# haasoscope_pro_adc_board_-_no_blind.net
KiCad netlist of a schematic drawn in EAGLE
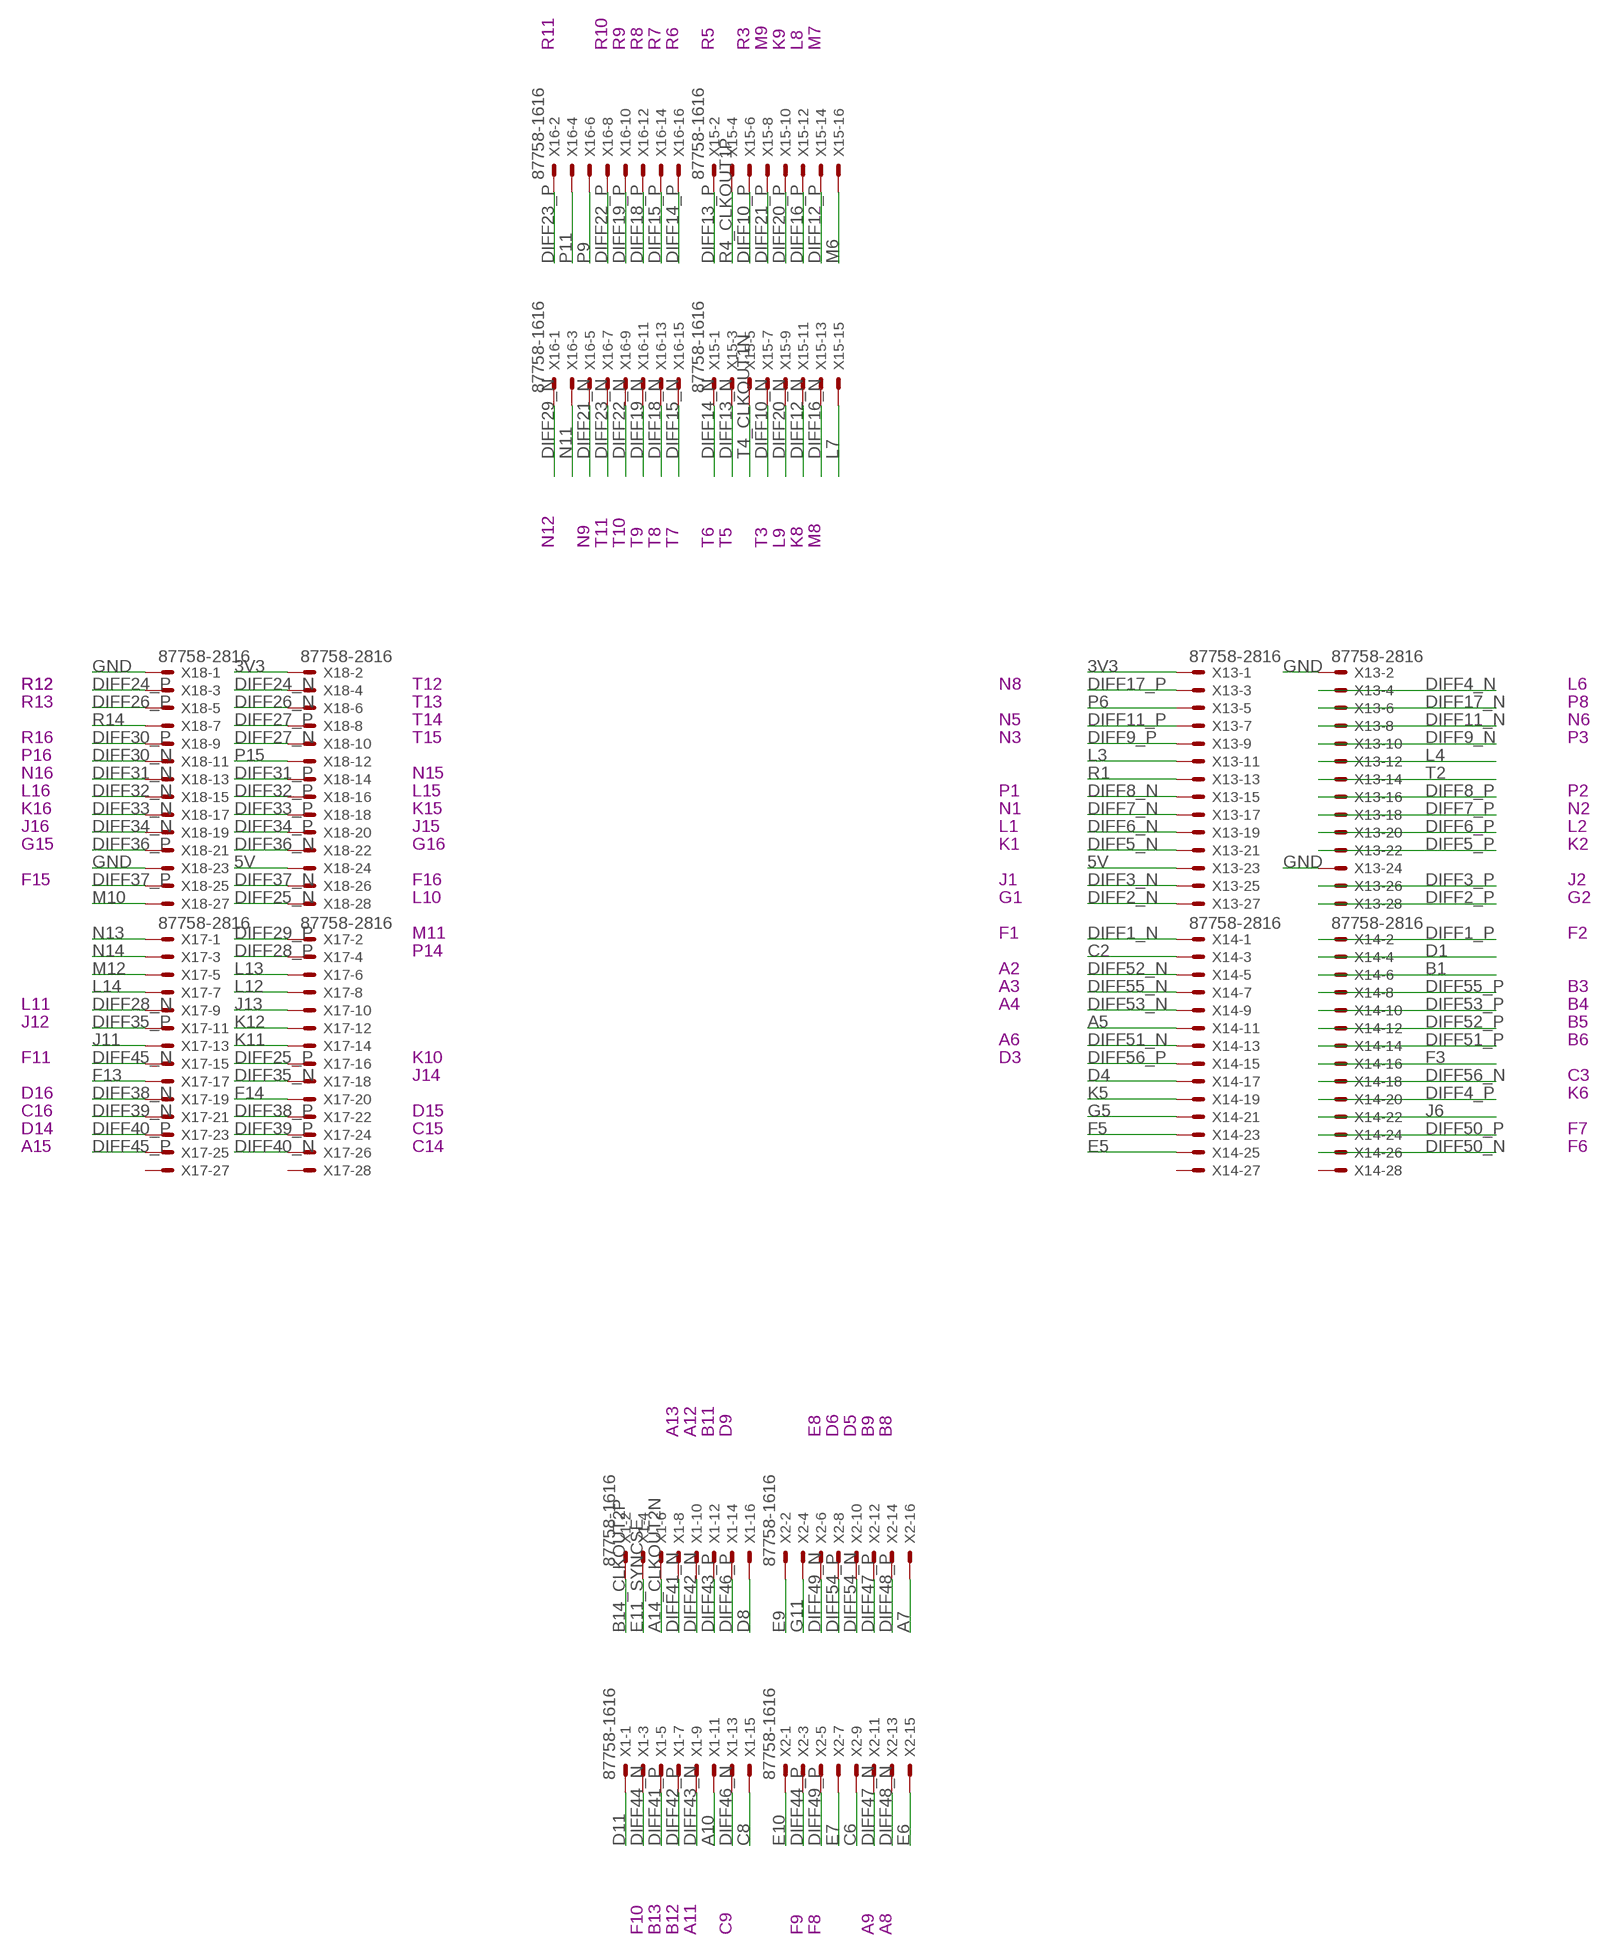
[diagram p0: schematic, sheet 1]
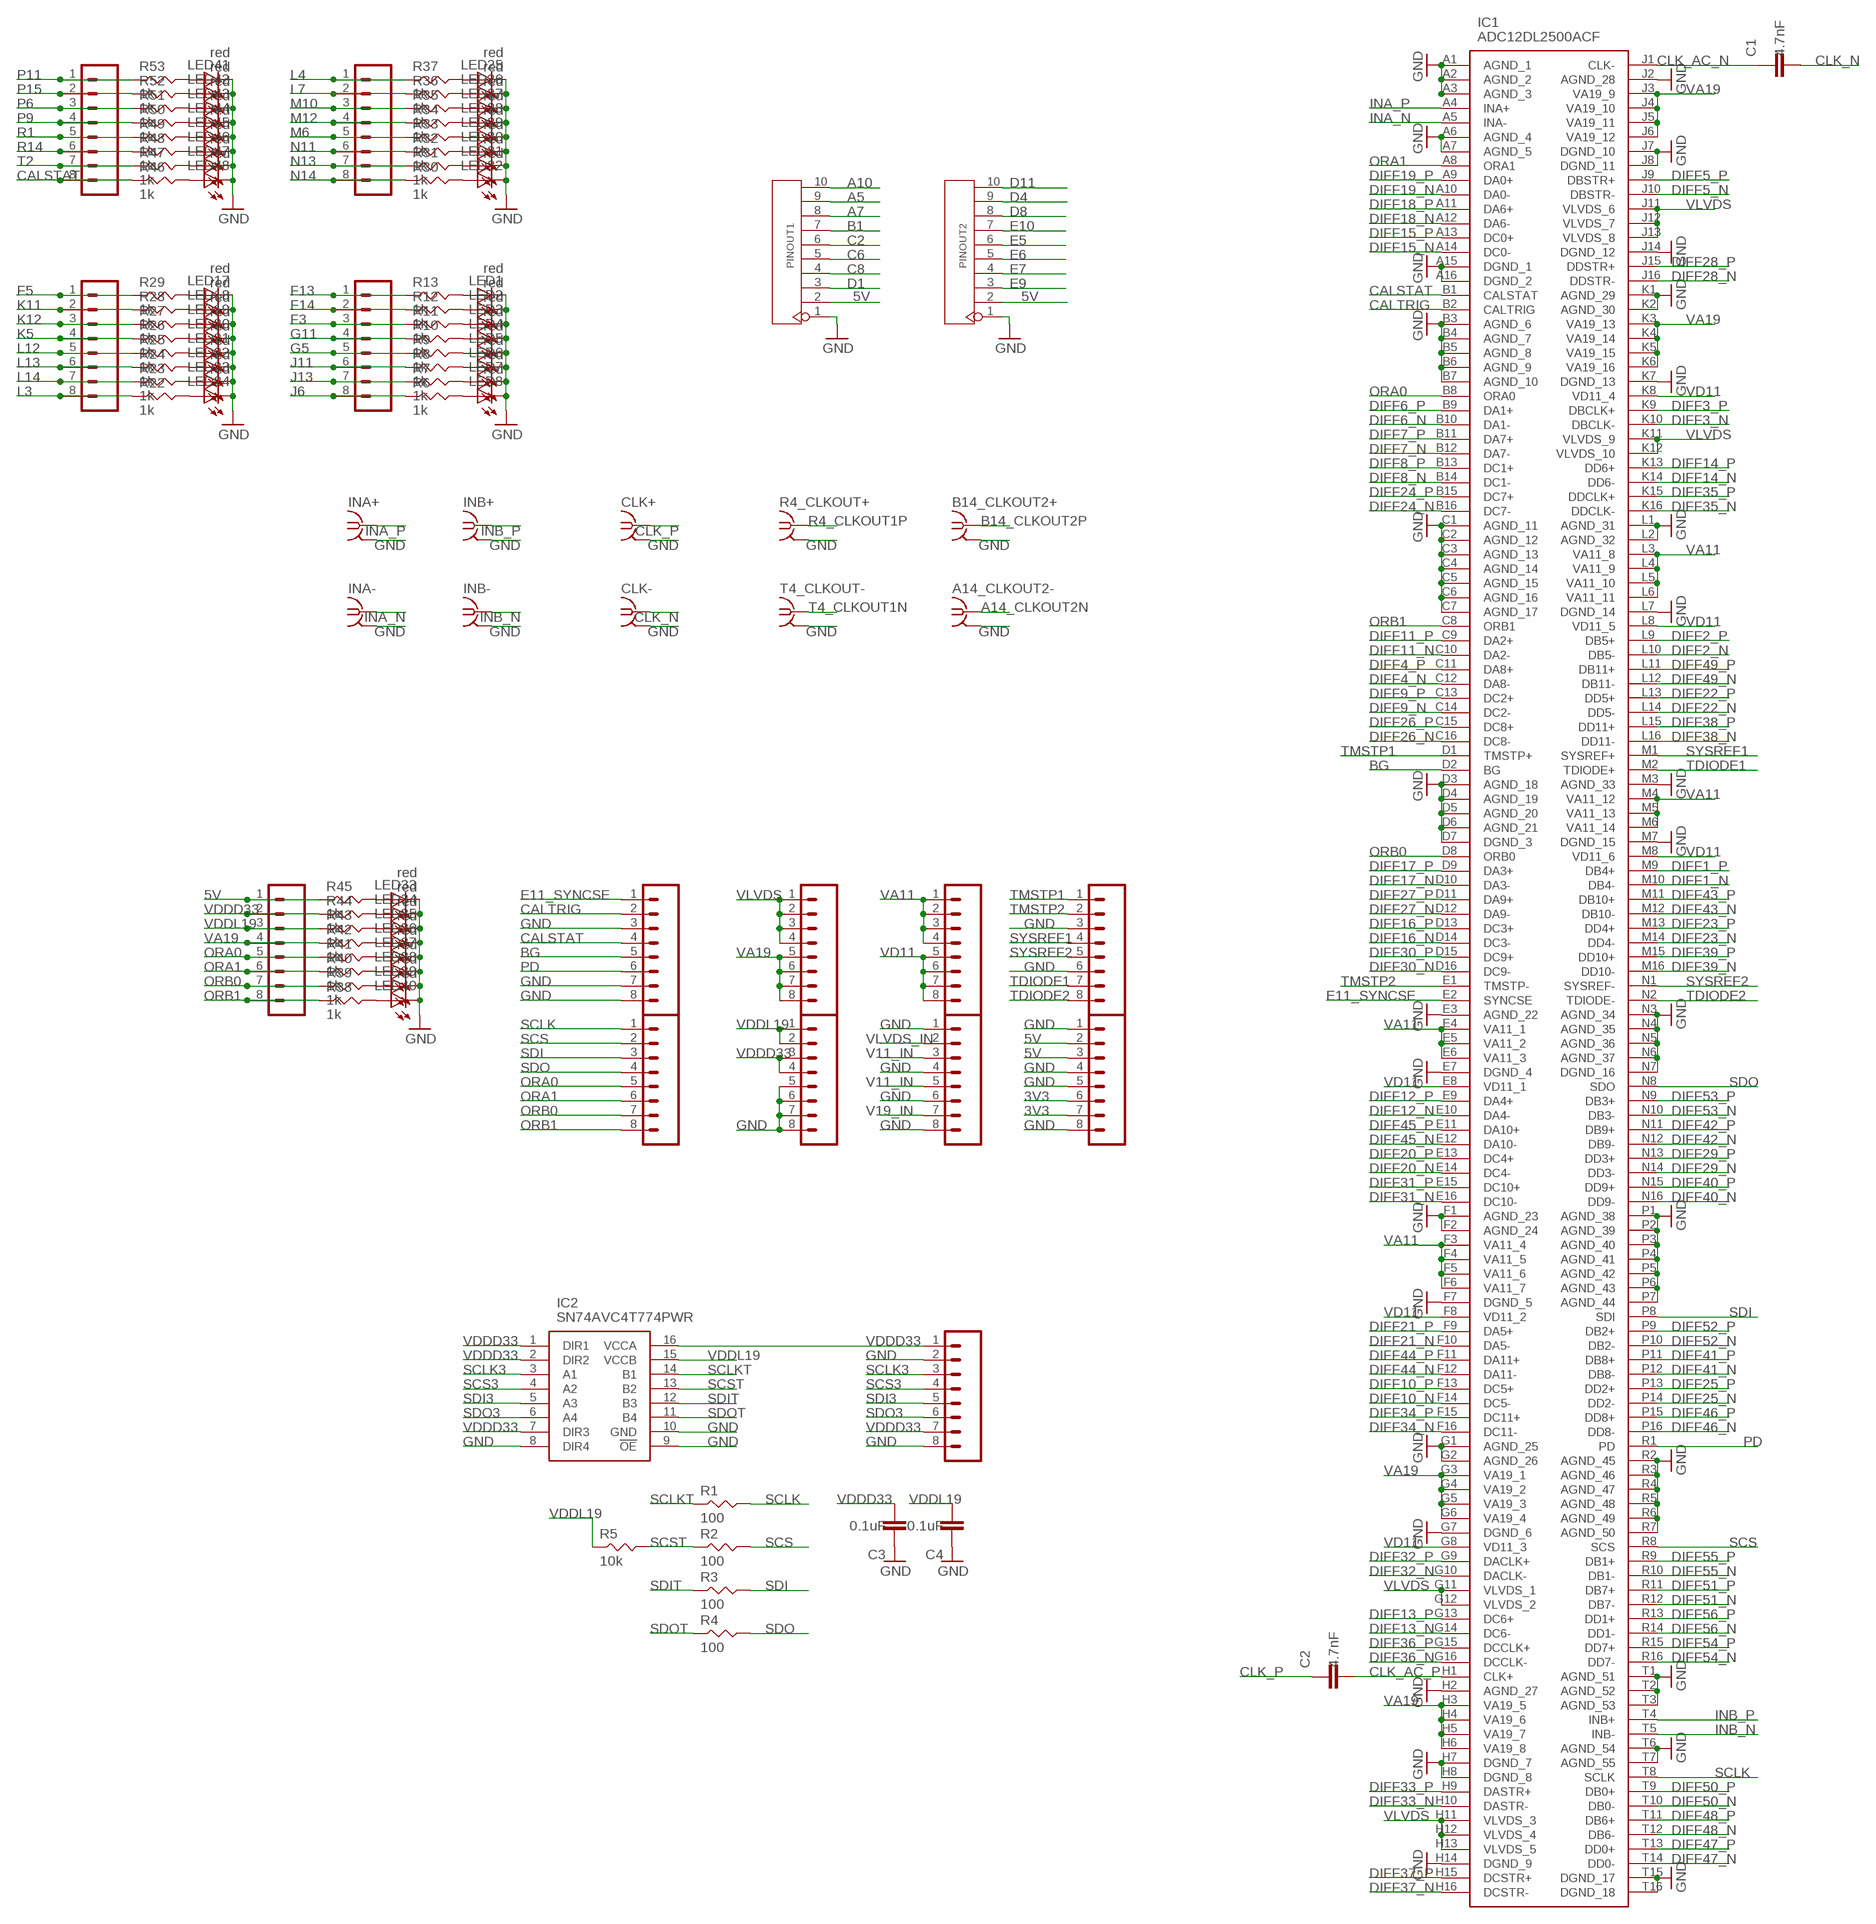
[diagram p1: schematic, sheet 2]
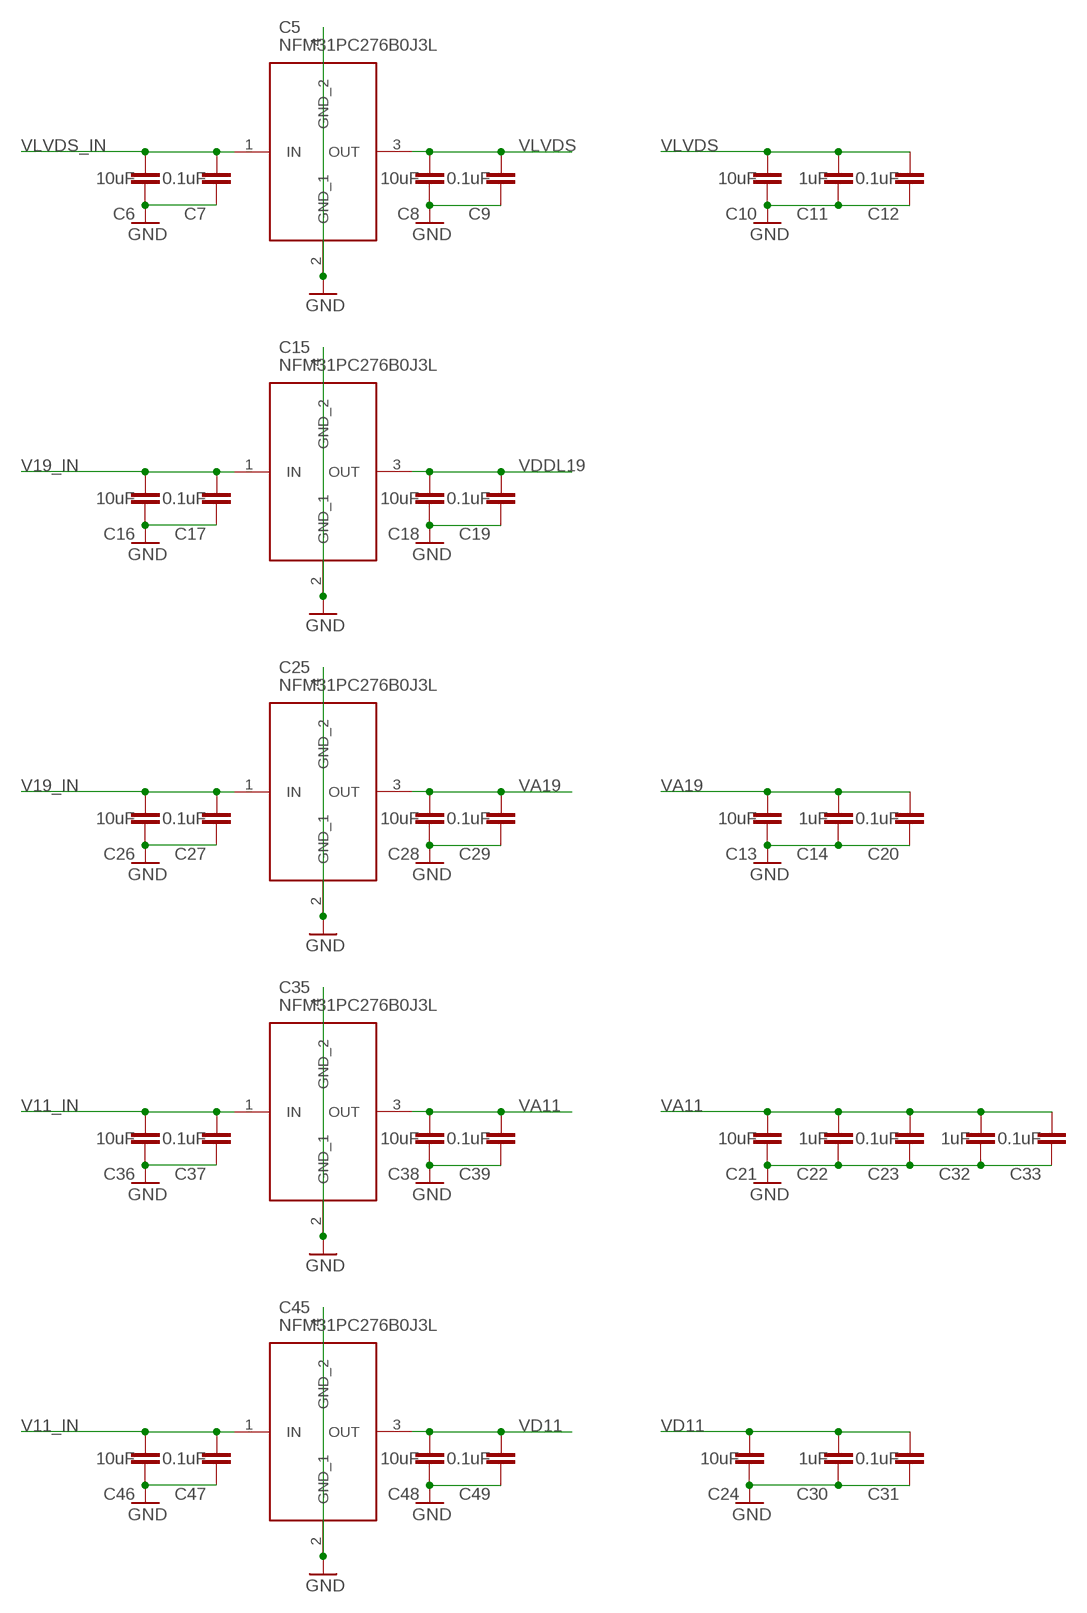
[diagram p2: schematic, sheet 3]

(export (version "E")
  (design (tool "Eeschema 10.0.6"))
  (components
    (comp (ref "C5")
      (value "NFM31PC276B0J3L")
      (footprint "eagle-import:NFM31HK103R1H3L")
      (fields (field (name "MOUSER_PART_NUMBER") "81-NFM31PC276B0J3L"))
      (libsource (lib "eagle-import") (part "NFM31PC276B0J3L"))
    )
    (comp (ref "C6")
      (value "10uF")
      (footprint "eagle-import:RESC0805_N")
      (libsource (lib "eagle-import") (part "CAPACITOR_0805_N"))
    )
    (comp (ref "C7")
      (value "0.1uF")
      (footprint "eagle-import:RESC0402_N")
      (libsource (lib "eagle-import") (part "CAPACITOR_0402_N"))
    )
    (comp (ref "C8")
      (value "10uF")
      (footprint "eagle-import:RESC0805_N")
      (libsource (lib "eagle-import") (part "CAPACITOR_0805_N"))
    )
    (comp (ref "C9")
      (value "0.1uF")
      (footprint "eagle-import:RESC0402_N")
      (libsource (lib "eagle-import") (part "CAPACITOR_0402_N"))
    )
    (comp (ref "C10")
      (value "10uF")
      (footprint "eagle-import:RESC0805_N")
      (libsource (lib "eagle-import") (part "CAPACITOR_0805_N"))
    )
    (comp (ref "C11")
      (value "1uF")
      (footprint "eagle-import:RESC0402_N")
      (libsource (lib "eagle-import") (part "CAPACITOR_0402_N"))
    )
    (comp (ref "C12")
      (value "0.1uF")
      (footprint "eagle-import:RESC0402_N")
      (libsource (lib "eagle-import") (part "CAPACITOR_0402_N"))
    )
    (comp (ref "C13")
      (value "10uF")
      (footprint "eagle-import:RESC0805_N")
      (libsource (lib "eagle-import") (part "CAPACITOR_0805_N"))
    )
    (comp (ref "C14")
      (value "1uF")
      (footprint "eagle-import:RESC0402_N")
      (libsource (lib "eagle-import") (part "CAPACITOR_0402_N"))
    )
    (comp (ref "C15")
      (value "NFM31PC276B0J3L")
      (footprint "eagle-import:NFM31HK103R1H3L")
      (fields (field (name "MOUSER_PART_NUMBER") "81-NFM31PC276B0J3L"))
      (libsource (lib "eagle-import") (part "NFM31PC276B0J3L"))
    )
    (comp (ref "C16")
      (value "10uF")
      (footprint "eagle-import:RESC0805_N")
      (libsource (lib "eagle-import") (part "CAPACITOR_0805_N"))
    )
    (comp (ref "C17")
      (value "0.1uF")
      (footprint "eagle-import:RESC0402_N")
      (libsource (lib "eagle-import") (part "CAPACITOR_0402_N"))
    )
    (comp (ref "C18")
      (value "10uF")
      (footprint "eagle-import:RESC0805_N")
      (libsource (lib "eagle-import") (part "CAPACITOR_0805_N"))
    )
    (comp (ref "C19")
      (value "0.1uF")
      (footprint "eagle-import:RESC0402_N")
      (libsource (lib "eagle-import") (part "CAPACITOR_0402_N"))
    )
    (comp (ref "C20")
      (value "0.1uF")
      (footprint "eagle-import:RESC0402_N")
      (libsource (lib "eagle-import") (part "CAPACITOR_0402_N"))
    )
    (comp (ref "C21")
      (value "10uF")
      (footprint "eagle-import:RESC0805_N")
      (libsource (lib "eagle-import") (part "CAPACITOR_0805_N"))
    )
    (comp (ref "C22")
      (value "1uF")
      (footprint "eagle-import:RESC0402_N")
      (libsource (lib "eagle-import") (part "CAPACITOR_0402_N"))
    )
    (comp (ref "C23")
      (value "0.1uF")
      (footprint "eagle-import:RESC0402_N")
      (libsource (lib "eagle-import") (part "CAPACITOR_0402_N"))
    )
    (comp (ref "C24")
      (value "10uF")
      (footprint "eagle-import:RESC0805_N")
      (libsource (lib "eagle-import") (part "CAPACITOR_0805_N"))
    )
    (comp (ref "C25")
      (value "NFM31PC276B0J3L")
      (footprint "eagle-import:NFM31HK103R1H3L")
      (fields (field (name "MOUSER_PART_NUMBER") "81-NFM31PC276B0J3L"))
      (libsource (lib "eagle-import") (part "NFM31PC276B0J3L"))
    )
    (comp (ref "C26")
      (value "10uF")
      (footprint "eagle-import:RESC0805_N")
      (libsource (lib "eagle-import") (part "CAPACITOR_0805_N"))
    )
    (comp (ref "C27")
      (value "0.1uF")
      (footprint "eagle-import:RESC0402_N")
      (libsource (lib "eagle-import") (part "CAPACITOR_0402_N"))
    )
    (comp (ref "C28")
      (value "10uF")
      (footprint "eagle-import:RESC0805_N")
      (libsource (lib "eagle-import") (part "CAPACITOR_0805_N"))
    )
    (comp (ref "C29")
      (value "0.1uF")
      (footprint "eagle-import:RESC0402_N")
      (libsource (lib "eagle-import") (part "CAPACITOR_0402_N"))
    )
    (comp (ref "C30")
      (value "1uF")
      (footprint "eagle-import:RESC0402_N")
      (libsource (lib "eagle-import") (part "CAPACITOR_0402_N"))
    )
    (comp (ref "C31")
      (value "0.1uF")
      (footprint "eagle-import:RESC0402_N")
      (libsource (lib "eagle-import") (part "CAPACITOR_0402_N"))
    )
    (comp (ref "C32")
      (value "1uF")
      (footprint "eagle-import:RESC0402_N")
      (libsource (lib "eagle-import") (part "CAPACITOR_0402_N"))
    )
    (comp (ref "C33")
      (value "0.1uF")
      (footprint "eagle-import:RESC0402_N")
      (libsource (lib "eagle-import") (part "CAPACITOR_0402_N"))
    )
    (comp (ref "C35")
      (value "NFM31PC276B0J3L")
      (footprint "eagle-import:NFM31HK103R1H3L")
      (fields (field (name "MOUSER_PART_NUMBER") "81-NFM31PC276B0J3L"))
      (libsource (lib "eagle-import") (part "NFM31PC276B0J3L"))
    )
    (comp (ref "C36")
      (value "10uF")
      (footprint "eagle-import:RESC0805_N")
      (libsource (lib "eagle-import") (part "CAPACITOR_0805_N"))
    )
    (comp (ref "C37")
      (value "0.1uF")
      (footprint "eagle-import:RESC0402_N")
      (libsource (lib "eagle-import") (part "CAPACITOR_0402_N"))
    )
    (comp (ref "C38")
      (value "10uF")
      (footprint "eagle-import:RESC0805_N")
      (libsource (lib "eagle-import") (part "CAPACITOR_0805_N"))
    )
    (comp (ref "C39")
      (value "0.1uF")
      (footprint "eagle-import:RESC0402_N")
      (libsource (lib "eagle-import") (part "CAPACITOR_0402_N"))
    )
    (comp (ref "C45")
      (value "NFM31PC276B0J3L")
      (footprint "eagle-import:NFM31HK103R1H3L")
      (fields (field (name "MOUSER_PART_NUMBER") "81-NFM31PC276B0J3L"))
      (libsource (lib "eagle-import") (part "NFM31PC276B0J3L"))
    )
    (comp (ref "C46")
      (value "10uF")
      (footprint "eagle-import:RESC0805_N")
      (libsource (lib "eagle-import") (part "CAPACITOR_0805_N"))
    )
    (comp (ref "C47")
      (value "0.1uF")
      (footprint "eagle-import:RESC0402_N")
      (libsource (lib "eagle-import") (part "CAPACITOR_0402_N"))
    )
    (comp (ref "C48")
      (value "10uF")
      (footprint "eagle-import:RESC0805_N")
      (libsource (lib "eagle-import") (part "CAPACITOR_0805_N"))
    )
    (comp (ref "C49")
      (value "0.1uF")
      (footprint "eagle-import:RESC0402_N")
      (libsource (lib "eagle-import") (part "CAPACITOR_0402_N"))
    )
    (comp (ref "X1")
      (value "87758-1616")
      (footprint "eagle-import:87758-1616")
      (fields (field (name "MF") "MOLEX"))
      (libsource (lib "eagle-import") (part "87758-1616"))
    )
    (comp (ref "X2")
      (value "87758-1616")
      (footprint "eagle-import:87758-1616")
      (fields (field (name "MF") "MOLEX"))
      (libsource (lib "eagle-import") (part "87758-1616"))
    )
    (comp (ref "X13")
      (value "87758-2816")
      (footprint "eagle-import:87758-2816")
      (fields (field (name "MF") "MOLEX"))
      (libsource (lib "eagle-import") (part "87758-2816"))
    )
    (comp (ref "X14")
      (value "87758-2816")
      (footprint "eagle-import:87758-2816")
      (fields (field (name "MF") "MOLEX"))
      (libsource (lib "eagle-import") (part "87758-2816"))
    )
    (comp (ref "X15")
      (value "87758-1616")
      (footprint "eagle-import:87758-1616")
      (fields (field (name "MF") "MOLEX"))
      (libsource (lib "eagle-import") (part "87758-1616"))
    )
    (comp (ref "X16")
      (value "87758-1616")
      (footprint "eagle-import:87758-1616")
      (fields (field (name "MF") "MOLEX"))
      (libsource (lib "eagle-import") (part "87758-1616"))
    )
    (comp (ref "X17")
      (value "87758-2816")
      (footprint "eagle-import:87758-2816")
      (fields (field (name "MF") "MOLEX"))
      (libsource (lib "eagle-import") (part "87758-2816"))
    )
    (comp (ref "X18")
      (value "87758-2816")
      (footprint "eagle-import:87758-2816")
      (fields (field (name "MF") "MOLEX"))
      (libsource (lib "eagle-import") (part "87758-2816"))
    )
    (comp (ref "A14_CLKOUT2-")
      (value "BU-SMB-V")
      (footprint "eagle-import:BU-SMB-V")
      (libsource (lib "eagle-import") (part "BU-SMB-V"))
    )
    (comp (ref "B14_CLKOUT2+")
      (value "BU-SMB-V")
      (footprint "eagle-import:BU-SMB-V")
      (libsource (lib "eagle-import") (part "BU-SMB-V"))
    )
    (comp (ref "C1")
      (value "4.7nF")
      (footprint "eagle-import:RESC0402_N")
      (libsource (lib "eagle-import") (part "CAPACITOR_0402_N"))
    )
    (comp (ref "C2")
      (value "4.7nF")
      (footprint "eagle-import:RESC0402_N")
      (libsource (lib "eagle-import") (part "CAPACITOR_0402_N"))
    )
    (comp (ref "C3")
      (value "0.1uF")
      (footprint "eagle-import:RESC0402_N")
      (libsource (lib "eagle-import") (part "CAPACITOR_0402_N"))
    )
    (comp (ref "C4")
      (value "0.1uF")
      (footprint "eagle-import:RESC0402_N")
      (libsource (lib "eagle-import") (part "CAPACITOR_0402_N"))
    )
    (comp (ref "CLK+")
      (value "BU-SMB-V")
      (footprint "eagle-import:BU-SMB-V")
      (libsource (lib "eagle-import") (part "BU-SMB-V"))
    )
    (comp (ref "CLK-")
      (value "BU-SMB-V")
      (footprint "eagle-import:BU-SMB-V")
      (libsource (lib "eagle-import") (part "BU-SMB-V"))
    )
    (comp (ref "IC1")
      (value "ADC12DL2500ACF")
      (footprint "eagle-import:BGA256C100P16X16_1700X1700X331")
      (fields (field (name "MANUFACTURER_PART_NUMBER") "ADC12DL500ACF"))
      (libsource (lib "eagle-import") (part "ADC12DL2500ACF"))
    )
    (comp (ref "IC2")
      (value "SN74AVC4T774PWR")
      (footprint "eagle-import:SOP65P640X120-16N")
      (fields (field (name "MOUSER_PART_NUMBER") "595-SN74AVC4T774PWR"))
      (libsource (lib "eagle-import") (part "SN74AVC4T774PWR"))
    )
    (comp (ref "INA+")
      (value "BU-SMB-V")
      (footprint "eagle-import:BU-SMB-V")
      (libsource (lib "eagle-import") (part "BU-SMB-V"))
    )
    (comp (ref "INA-")
      (value "BU-SMB-V")
      (footprint "eagle-import:BU-SMB-V")
      (libsource (lib "eagle-import") (part "BU-SMB-V"))
    )
    (comp (ref "INB+")
      (value "BU-SMB-V")
      (footprint "eagle-import:BU-SMB-V")
      (libsource (lib "eagle-import") (part "BU-SMB-V"))
    )
    (comp (ref "INB-")
      (value "BU-SMB-V")
      (footprint "eagle-import:BU-SMB-V")
      (libsource (lib "eagle-import") (part "BU-SMB-V"))
    )
    (comp (ref "J1")
      (value "8pin")
      (footprint "eagle-import:1X08")
      (libsource (lib "eagle-import") (part "CONN_08{dblquote}"))
    )
    (comp (ref "J2")
      (value "8pin")
      (footprint "eagle-import:1X08")
      (libsource (lib "eagle-import") (part "CONN_08{dblquote}"))
    )
    (comp (ref "J3")
      (value "8pin")
      (footprint "eagle-import:1X08")
      (libsource (lib "eagle-import") (part "CONN_08{dblquote}"))
    )
    (comp (ref "J4")
      (value "8pin")
      (footprint "eagle-import:1X08")
      (libsource (lib "eagle-import") (part "CONN_08{dblquote}"))
    )
    (comp (ref "J5")
      (value "8pin")
      (footprint "eagle-import:1X08")
      (libsource (lib "eagle-import") (part "CONN_08{dblquote}"))
    )
    (comp (ref "J6")
      (value "8pin")
      (footprint "eagle-import:1X08")
      (libsource (lib "eagle-import") (part "CONN_08{dblquote}"))
    )
    (comp (ref "J7")
      (value "8pin")
      (footprint "eagle-import:1X08")
      (libsource (lib "eagle-import") (part "CONN_08{dblquote}"))
    )
    (comp (ref "J8")
      (value "8pin")
      (footprint "eagle-import:1X08")
      (libsource (lib "eagle-import") (part "CONN_08{dblquote}"))
    )
    (comp (ref "J10")
      (value "8pin")
      (footprint "eagle-import:1X08")
      (libsource (lib "eagle-import") (part "CONN_08{dblquote}"))
    )
    (comp (ref "J11")
      (value "8pin")
      (footprint "eagle-import:1X08")
      (libsource (lib "eagle-import") (part "CONN_08{dblquote}"))
    )
    (comp (ref "J12")
      (value "8pin")
      (footprint "eagle-import:1X08")
      (libsource (lib "eagle-import") (part "CONN_08{dblquote}"))
    )
    (comp (ref "J13")
      (value "8pin")
      (footprint "eagle-import:1X08")
      (libsource (lib "eagle-import") (part "CONN_08{dblquote}"))
    )
    (comp (ref "J16")
      (value "8pin")
      (footprint "eagle-import:1X08")
      (libsource (lib "eagle-import") (part "CONN_08{dblquote}"))
    )
    (comp (ref "J17")
      (value "8pin")
      (footprint "eagle-import:1X08")
      (libsource (lib "eagle-import") (part "CONN_08{dblquote}"))
    )
    (comp (ref "LED1")
      (value "red")
      (footprint "eagle-import:CHIP-LED0603")
      (libsource (lib "eagle-import") (part "LEDCHIP-LED0603"))
    )
    (comp (ref "LED2")
      (value "red")
      (footprint "eagle-import:CHIP-LED0603")
      (libsource (lib "eagle-import") (part "LEDCHIP-LED0603"))
    )
    (comp (ref "LED3")
      (value "red")
      (footprint "eagle-import:CHIP-LED0603")
      (libsource (lib "eagle-import") (part "LEDCHIP-LED0603"))
    )
    (comp (ref "LED4")
      (value "red")
      (footprint "eagle-import:CHIP-LED0603")
      (libsource (lib "eagle-import") (part "LEDCHIP-LED0603"))
    )
    (comp (ref "LED5")
      (value "red")
      (footprint "eagle-import:CHIP-LED0603")
      (libsource (lib "eagle-import") (part "LEDCHIP-LED0603"))
    )
    (comp (ref "LED6")
      (value "red")
      (footprint "eagle-import:CHIP-LED0603")
      (libsource (lib "eagle-import") (part "LEDCHIP-LED0603"))
    )
    (comp (ref "LED7")
      (value "red")
      (footprint "eagle-import:CHIP-LED0603")
      (libsource (lib "eagle-import") (part "LEDCHIP-LED0603"))
    )
    (comp (ref "LED8")
      (value "red")
      (footprint "eagle-import:CHIP-LED0603")
      (libsource (lib "eagle-import") (part "LEDCHIP-LED0603"))
    )
    (comp (ref "LED17")
      (value "red")
      (footprint "eagle-import:CHIP-LED0603")
      (libsource (lib "eagle-import") (part "LEDCHIP-LED0603"))
    )
    (comp (ref "LED18")
      (value "red")
      (footprint "eagle-import:CHIP-LED0603")
      (libsource (lib "eagle-import") (part "LEDCHIP-LED0603"))
    )
    (comp (ref "LED19")
      (value "red")
      (footprint "eagle-import:CHIP-LED0603")
      (libsource (lib "eagle-import") (part "LEDCHIP-LED0603"))
    )
    (comp (ref "LED20")
      (value "red")
      (footprint "eagle-import:CHIP-LED0603")
      (libsource (lib "eagle-import") (part "LEDCHIP-LED0603"))
    )
    (comp (ref "LED21")
      (value "red")
      (footprint "eagle-import:CHIP-LED0603")
      (libsource (lib "eagle-import") (part "LEDCHIP-LED0603"))
    )
    (comp (ref "LED22")
      (value "red")
      (footprint "eagle-import:CHIP-LED0603")
      (libsource (lib "eagle-import") (part "LEDCHIP-LED0603"))
    )
    (comp (ref "LED23")
      (value "red")
      (footprint "eagle-import:CHIP-LED0603")
      (libsource (lib "eagle-import") (part "LEDCHIP-LED0603"))
    )
    (comp (ref "LED24")
      (value "red")
      (footprint "eagle-import:CHIP-LED0603")
      (libsource (lib "eagle-import") (part "LEDCHIP-LED0603"))
    )
    (comp (ref "LED25")
      (value "red")
      (footprint "eagle-import:CHIP-LED0603")
      (libsource (lib "eagle-import") (part "LEDCHIP-LED0603"))
    )
    (comp (ref "LED26")
      (value "red")
      (footprint "eagle-import:CHIP-LED0603")
      (libsource (lib "eagle-import") (part "LEDCHIP-LED0603"))
    )
    (comp (ref "LED27")
      (value "red")
      (footprint "eagle-import:CHIP-LED0603")
      (libsource (lib "eagle-import") (part "LEDCHIP-LED0603"))
    )
    (comp (ref "LED28")
      (value "red")
      (footprint "eagle-import:CHIP-LED0603")
      (libsource (lib "eagle-import") (part "LEDCHIP-LED0603"))
    )
    (comp (ref "LED29")
      (value "red")
      (footprint "eagle-import:CHIP-LED0603")
      (libsource (lib "eagle-import") (part "LEDCHIP-LED0603"))
    )
    (comp (ref "LED30")
      (value "red")
      (footprint "eagle-import:CHIP-LED0603")
      (libsource (lib "eagle-import") (part "LEDCHIP-LED0603"))
    )
    (comp (ref "LED31")
      (value "red")
      (footprint "eagle-import:CHIP-LED0603")
      (libsource (lib "eagle-import") (part "LEDCHIP-LED0603"))
    )
    (comp (ref "LED32")
      (value "red")
      (footprint "eagle-import:CHIP-LED0603")
      (libsource (lib "eagle-import") (part "LEDCHIP-LED0603"))
    )
    (comp (ref "LED33")
      (value "red")
      (footprint "eagle-import:CHIP-LED0603")
      (libsource (lib "eagle-import") (part "LEDCHIP-LED0603"))
    )
    (comp (ref "LED34")
      (value "red")
      (footprint "eagle-import:CHIP-LED0603")
      (libsource (lib "eagle-import") (part "LEDCHIP-LED0603"))
    )
    (comp (ref "LED35")
      (value "red")
      (footprint "eagle-import:CHIP-LED0603")
      (libsource (lib "eagle-import") (part "LEDCHIP-LED0603"))
    )
    (comp (ref "LED36")
      (value "red")
      (footprint "eagle-import:CHIP-LED0603")
      (libsource (lib "eagle-import") (part "LEDCHIP-LED0603"))
    )
    (comp (ref "LED37")
      (value "red")
      (footprint "eagle-import:CHIP-LED0603")
      (libsource (lib "eagle-import") (part "LEDCHIP-LED0603"))
    )
    (comp (ref "LED38")
      (value "red")
      (footprint "eagle-import:CHIP-LED0603")
      (libsource (lib "eagle-import") (part "LEDCHIP-LED0603"))
    )
    (comp (ref "LED39")
      (value "red")
      (footprint "eagle-import:CHIP-LED0603")
      (libsource (lib "eagle-import") (part "LEDCHIP-LED0603"))
    )
    (comp (ref "LED40")
      (value "red")
      (footprint "eagle-import:CHIP-LED0603")
      (libsource (lib "eagle-import") (part "LEDCHIP-LED0603"))
    )
    (comp (ref "LED41")
      (value "red")
      (footprint "eagle-import:CHIP-LED0603")
      (libsource (lib "eagle-import") (part "LEDCHIP-LED0603"))
    )
    (comp (ref "LED42")
      (value "red")
      (footprint "eagle-import:CHIP-LED0603")
      (libsource (lib "eagle-import") (part "LEDCHIP-LED0603"))
    )
    (comp (ref "LED43")
      (value "red")
      (footprint "eagle-import:CHIP-LED0603")
      (libsource (lib "eagle-import") (part "LEDCHIP-LED0603"))
    )
    (comp (ref "LED44")
      (value "red")
      (footprint "eagle-import:CHIP-LED0603")
      (libsource (lib "eagle-import") (part "LEDCHIP-LED0603"))
    )
    (comp (ref "LED45")
      (value "red")
      (footprint "eagle-import:CHIP-LED0603")
      (libsource (lib "eagle-import") (part "LEDCHIP-LED0603"))
    )
    (comp (ref "LED46")
      (value "red")
      (footprint "eagle-import:CHIP-LED0603")
      (libsource (lib "eagle-import") (part "LEDCHIP-LED0603"))
    )
    (comp (ref "LED47")
      (value "red")
      (footprint "eagle-import:CHIP-LED0603")
      (libsource (lib "eagle-import") (part "LEDCHIP-LED0603"))
    )
    (comp (ref "LED48")
      (value "red")
      (footprint "eagle-import:CHIP-LED0603")
      (libsource (lib "eagle-import") (part "LEDCHIP-LED0603"))
    )
    (comp (ref "PINOUT1")
      (value "YELLOW-10P-2.54")
      (footprint "eagle-import:H10-2.54")
      (fields (field (name "MPN") "F185-1110A1BSYC1"))
      (libsource (lib "eagle-import") (part "DIP-YELLOW-FEMALE-HEADER-VERT(10P-2.54)"))
    )
    (comp (ref "PINOUT2")
      (value "YELLOW-10P-2.54")
      (footprint "eagle-import:H10-2.54")
      (fields (field (name "MPN") "F185-1110A1BSYC1"))
      (libsource (lib "eagle-import") (part "DIP-YELLOW-FEMALE-HEADER-VERT(10P-2.54)"))
    )
    (comp (ref "R1")
      (value "100")
      (footprint "eagle-import:RES-0402")
      (libsource (lib "eagle-import") (part "RES-0402"))
    )
    (comp (ref "R2")
      (value "100")
      (footprint "eagle-import:RES-0402")
      (libsource (lib "eagle-import") (part "RES-0402"))
    )
    (comp (ref "R3")
      (value "100")
      (footprint "eagle-import:RES-0402")
      (libsource (lib "eagle-import") (part "RES-0402"))
    )
    (comp (ref "R4")
      (value "100")
      (footprint "eagle-import:RES-0402")
      (libsource (lib "eagle-import") (part "RES-0402"))
    )
    (comp (ref "R4_CLKOUT+")
      (value "BU-SMB-V")
      (footprint "eagle-import:BU-SMB-V")
      (libsource (lib "eagle-import") (part "BU-SMB-V"))
    )
    (comp (ref "R5")
      (value "10k")
      (footprint "eagle-import:RES-0402")
      (libsource (lib "eagle-import") (part "RES-0402"))
    )
    (comp (ref "R6")
      (value "1k")
      (footprint "eagle-import:RES-0402")
      (libsource (lib "eagle-import") (part "RES-0402"))
    )
    (comp (ref "R7")
      (value "1k")
      (footprint "eagle-import:RES-0402")
      (libsource (lib "eagle-import") (part "RES-0402"))
    )
    (comp (ref "R8")
      (value "1k")
      (footprint "eagle-import:RES-0402")
      (libsource (lib "eagle-import") (part "RES-0402"))
    )
    (comp (ref "R9")
      (value "1k")
      (footprint "eagle-import:RES-0402")
      (libsource (lib "eagle-import") (part "RES-0402"))
    )
    (comp (ref "R10")
      (value "1k")
      (footprint "eagle-import:RES-0402")
      (libsource (lib "eagle-import") (part "RES-0402"))
    )
    (comp (ref "R11")
      (value "1k")
      (footprint "eagle-import:RES-0402")
      (libsource (lib "eagle-import") (part "RES-0402"))
    )
    (comp (ref "R12")
      (value "1k")
      (footprint "eagle-import:RES-0402")
      (libsource (lib "eagle-import") (part "RES-0402"))
    )
    (comp (ref "R13")
      (value "1k")
      (footprint "eagle-import:RES-0402")
      (libsource (lib "eagle-import") (part "RES-0402"))
    )
    (comp (ref "R22")
      (value "1k")
      (footprint "eagle-import:RES-0402")
      (libsource (lib "eagle-import") (part "RES-0402"))
    )
    (comp (ref "R23")
      (value "1k")
      (footprint "eagle-import:RES-0402")
      (libsource (lib "eagle-import") (part "RES-0402"))
    )
    (comp (ref "R24")
      (value "1k")
      (footprint "eagle-import:RES-0402")
      (libsource (lib "eagle-import") (part "RES-0402"))
    )
    (comp (ref "R25")
      (value "1k")
      (footprint "eagle-import:RES-0402")
      (libsource (lib "eagle-import") (part "RES-0402"))
    )
    (comp (ref "R26")
      (value "1k")
      (footprint "eagle-import:RES-0402")
      (libsource (lib "eagle-import") (part "RES-0402"))
    )
    (comp (ref "R27")
      (value "1k")
      (footprint "eagle-import:RES-0402")
      (libsource (lib "eagle-import") (part "RES-0402"))
    )
    (comp (ref "R28")
      (value "1k")
      (footprint "eagle-import:RES-0402")
      (libsource (lib "eagle-import") (part "RES-0402"))
    )
    (comp (ref "R29")
      (value "1k")
      (footprint "eagle-import:RES-0402")
      (libsource (lib "eagle-import") (part "RES-0402"))
    )
    (comp (ref "R30")
      (value "1k")
      (footprint "eagle-import:RES-0402")
      (libsource (lib "eagle-import") (part "RES-0402"))
    )
    (comp (ref "R31")
      (value "1k")
      (footprint "eagle-import:RES-0402")
      (libsource (lib "eagle-import") (part "RES-0402"))
    )
    (comp (ref "R32")
      (value "1k")
      (footprint "eagle-import:RES-0402")
      (libsource (lib "eagle-import") (part "RES-0402"))
    )
    (comp (ref "R33")
      (value "1k")
      (footprint "eagle-import:RES-0402")
      (libsource (lib "eagle-import") (part "RES-0402"))
    )
    (comp (ref "R34")
      (value "1k")
      (footprint "eagle-import:RES-0402")
      (libsource (lib "eagle-import") (part "RES-0402"))
    )
    (comp (ref "R35")
      (value "1k")
      (footprint "eagle-import:RES-0402")
      (libsource (lib "eagle-import") (part "RES-0402"))
    )
    (comp (ref "R36")
      (value "1k")
      (footprint "eagle-import:RES-0402")
      (libsource (lib "eagle-import") (part "RES-0402"))
    )
    (comp (ref "R37")
      (value "1k")
      (footprint "eagle-import:RES-0402")
      (libsource (lib "eagle-import") (part "RES-0402"))
    )
    (comp (ref "R38")
      (value "1k")
      (footprint "eagle-import:RES-0402")
      (libsource (lib "eagle-import") (part "RES-0402"))
    )
    (comp (ref "R39")
      (value "1k")
      (footprint "eagle-import:RES-0402")
      (libsource (lib "eagle-import") (part "RES-0402"))
    )
    (comp (ref "R40")
      (value "1k")
      (footprint "eagle-import:RES-0402")
      (libsource (lib "eagle-import") (part "RES-0402"))
    )
    (comp (ref "R41")
      (value "1k")
      (footprint "eagle-import:RES-0402")
      (libsource (lib "eagle-import") (part "RES-0402"))
    )
    (comp (ref "R42")
      (value "1k")
      (footprint "eagle-import:RES-0402")
      (libsource (lib "eagle-import") (part "RES-0402"))
    )
    (comp (ref "R43")
      (value "1k")
      (footprint "eagle-import:RES-0402")
      (libsource (lib "eagle-import") (part "RES-0402"))
    )
    (comp (ref "R44")
      (value "1k")
      (footprint "eagle-import:RES-0402")
      (libsource (lib "eagle-import") (part "RES-0402"))
    )
    (comp (ref "R45")
      (value "1k")
      (footprint "eagle-import:RES-0402")
      (libsource (lib "eagle-import") (part "RES-0402"))
    )
    (comp (ref "R46")
      (value "1k")
      (footprint "eagle-import:RES-0402")
      (libsource (lib "eagle-import") (part "RES-0402"))
    )
    (comp (ref "R47")
      (value "1k")
      (footprint "eagle-import:RES-0402")
      (libsource (lib "eagle-import") (part "RES-0402"))
    )
    (comp (ref "R48")
      (value "1k")
      (footprint "eagle-import:RES-0402")
      (libsource (lib "eagle-import") (part "RES-0402"))
    )
    (comp (ref "R49")
      (value "1k")
      (footprint "eagle-import:RES-0402")
      (libsource (lib "eagle-import") (part "RES-0402"))
    )
    (comp (ref "R50")
      (value "1k")
      (footprint "eagle-import:RES-0402")
      (libsource (lib "eagle-import") (part "RES-0402"))
    )
    (comp (ref "R51")
      (value "1k")
      (footprint "eagle-import:RES-0402")
      (libsource (lib "eagle-import") (part "RES-0402"))
    )
    (comp (ref "R52")
      (value "1k")
      (footprint "eagle-import:RES-0402")
      (libsource (lib "eagle-import") (part "RES-0402"))
    )
    (comp (ref "R53")
      (value "1k")
      (footprint "eagle-import:RES-0402")
      (libsource (lib "eagle-import") (part "RES-0402"))
    )
    (comp (ref "T4_CLKOUT-")
      (value "BU-SMB-V")
      (footprint "eagle-import:BU-SMB-V")
      (libsource (lib "eagle-import") (part "BU-SMB-V"))
    )
  )
  (nets
    (net (code "1") (name "3V3") (class "Default")
      (node (ref "J6") (pin "6") (pinfunction "6_6") (pintype "passive"))
      (node (ref "J6") (pin "7") (pinfunction "7_7") (pintype "passive"))
      (node (ref "X13") (pin "1") (pinfunction "S_1") (pintype "passive"))
      (node (ref "X18") (pin "2") (pinfunction "S_2") (pintype "passive"))
    )
    (net (code "2") (name "5V") (class "Default")
      (node (ref "J12") (pin "1") (pinfunction "1_1") (pintype "passive"))
      (node (ref "J6") (pin "2") (pinfunction "2_2") (pintype "passive"))
      (node (ref "J6") (pin "3") (pinfunction "3_3") (pintype "passive"))
      (node (ref "PINOUT1") (pin "2") (pinfunction "2_2") (pintype "bidirectional"))
      (node (ref "PINOUT2") (pin "2") (pinfunction "2_2") (pintype "bidirectional"))
      (node (ref "R45") (pin "P$1") (pinfunction "P$1_P$1") (pintype "bidirectional"))
      (node (ref "X13") (pin "23") (pinfunction "S_23") (pintype "passive"))
      (node (ref "X18") (pin "24") (pinfunction "S_24") (pintype "passive"))
    )
    (net (code "3") (name "A5") (class "Default")
      (node (ref "PINOUT1") (pin "9") (pinfunction "9_9") (pintype "bidirectional"))
      (node (ref "X14") (pin "11") (pinfunction "S_11") (pintype "passive"))
    )
    (net (code "4") (name "A7") (class "Default")
      (node (ref "PINOUT1") (pin "8") (pinfunction "8_8") (pintype "bidirectional"))
      (node (ref "X2") (pin "16") (pinfunction "S_16") (pintype "passive"))
    )
    (net (code "5") (name "A10") (class "Default")
      (node (ref "PINOUT1") (pin "10") (pinfunction "10_10") (pintype "bidirectional"))
      (node (ref "X1") (pin "11") (pinfunction "S_11") (pintype "passive"))
    )
    (net (code "6") (name "A14_CLKOUT2N") (class "Default")
      (node (ref "A14_CLKOUT2-") (pin "1") (pinfunction "1_1") (pintype "passive"))
      (node (ref "X1") (pin "6") (pinfunction "S_6") (pintype "passive"))
    )
    (net (code "7") (name "B1") (class "Default")
      (node (ref "PINOUT1") (pin "7") (pinfunction "7_7") (pintype "bidirectional"))
      (node (ref "X14") (pin "6") (pinfunction "S_6") (pintype "passive"))
    )
    (net (code "8") (name "B14_CLKOUT2P") (class "Default")
      (node (ref "B14_CLKOUT2+") (pin "1") (pinfunction "1_1") (pintype "passive"))
      (node (ref "X1") (pin "2") (pinfunction "S_2") (pintype "passive"))
    )
    (net (code "9") (name "BG") (class "Default")
      (node (ref "IC1") (pin "D2") (pinfunction "BG_D2") (pintype "bidirectional"))
      (node (ref "J17") (pin "5") (pinfunction "5_5") (pintype "passive"))
    )
    (net (code "10") (name "C2") (class "Default")
      (node (ref "PINOUT1") (pin "6") (pinfunction "6_6") (pintype "bidirectional"))
      (node (ref "X14") (pin "3") (pinfunction "S_3") (pintype "passive"))
    )
    (net (code "11") (name "C6") (class "Default")
      (node (ref "PINOUT1") (pin "5") (pinfunction "5_5") (pintype "bidirectional"))
      (node (ref "X2") (pin "9") (pinfunction "S_9") (pintype "passive"))
    )
    (net (code "12") (name "C8") (class "Default")
      (node (ref "PINOUT1") (pin "4") (pinfunction "4_4") (pintype "bidirectional"))
      (node (ref "X1") (pin "15") (pinfunction "S_15") (pintype "passive"))
    )
    (net (code "13") (name "CALSTAT") (class "Default")
      (node (ref "IC1") (pin "B1") (pinfunction "CALSTAT_B1") (pintype "bidirectional"))
      (node (ref "J13") (pin "8") (pinfunction "8_8") (pintype "passive"))
      (node (ref "J17") (pin "4") (pinfunction "4_4") (pintype "passive"))
      (node (ref "R46") (pin "P$1") (pinfunction "P$1_P$1") (pintype "bidirectional"))
    )
    (net (code "14") (name "CALTRIG") (class "Default")
      (node (ref "IC1") (pin "B2") (pinfunction "CALTRIG_B2") (pintype "bidirectional"))
      (node (ref "J17") (pin "2") (pinfunction "2_2") (pintype "passive"))
    )
    (net (code "15") (name "CLK_AC_N") (class "Default")
      (node (ref "C1") (pin "1") (pinfunction "1_1") (pintype "passive"))
      (node (ref "IC1") (pin "J1") (pinfunction "CLK-_J1") (pintype "bidirectional"))
    )
    (net (code "16") (name "CLK_AC_P") (class "Default")
      (node (ref "C2") (pin "2") (pinfunction "2_2") (pintype "passive"))
      (node (ref "IC1") (pin "H1") (pinfunction "CLK+_H1") (pintype "bidirectional"))
    )
    (net (code "17") (name "CLK_N") (class "Default")
      (node (ref "C1") (pin "2") (pinfunction "2_2") (pintype "passive"))
      (node (ref "CLK-") (pin "1") (pinfunction "1_1") (pintype "passive"))
    )
    (net (code "18") (name "CLK_P") (class "Default")
      (node (ref "C2") (pin "1") (pinfunction "1_1") (pintype "passive"))
      (node (ref "CLK+") (pin "1") (pinfunction "1_1") (pintype "passive"))
    )
    (net (code "19") (name "D1") (class "Default")
      (node (ref "PINOUT1") (pin "3") (pinfunction "3_3") (pintype "bidirectional"))
      (node (ref "X14") (pin "4") (pinfunction "S_4") (pintype "passive"))
    )
    (net (code "20") (name "D4") (class "Default")
      (node (ref "PINOUT2") (pin "9") (pinfunction "9_9") (pintype "bidirectional"))
      (node (ref "X14") (pin "17") (pinfunction "S_17") (pintype "passive"))
    )
    (net (code "21") (name "D8") (class "Default")
      (node (ref "PINOUT2") (pin "8") (pinfunction "8_8") (pintype "bidirectional"))
      (node (ref "X1") (pin "16") (pinfunction "S_16") (pintype "passive"))
    )
    (net (code "22") (name "D11") (class "Default")
      (node (ref "PINOUT2") (pin "10") (pinfunction "10_10") (pintype "bidirectional"))
      (node (ref "X1") (pin "1") (pinfunction "S_1") (pintype "passive"))
    )
    (net (code "23") (name "DIFF1_N") (class "Default")
      (node (ref "IC1") (pin "M10") (pinfunction "DB4-_M10") (pintype "bidirectional"))
      (node (ref "X14") (pin "1") (pinfunction "S_1") (pintype "passive"))
    )
    (net (code "24") (name "DIFF1_P") (class "Default")
      (node (ref "IC1") (pin "M9") (pinfunction "DB4+_M9") (pintype "bidirectional"))
      (node (ref "X14") (pin "2") (pinfunction "S_2") (pintype "passive"))
    )
    (net (code "25") (name "DIFF2_N") (class "Default")
      (node (ref "IC1") (pin "L10") (pinfunction "DB5-_L10") (pintype "bidirectional"))
      (node (ref "X13") (pin "27") (pinfunction "S_27") (pintype "passive"))
    )
    (net (code "26") (name "DIFF2_P") (class "Default")
      (node (ref "IC1") (pin "L9") (pinfunction "DB5+_L9") (pintype "bidirectional"))
      (node (ref "X13") (pin "28") (pinfunction "S_28") (pintype "passive"))
    )
    (net (code "27") (name "DIFF3_N") (class "Default")
      (node (ref "IC1") (pin "K10") (pinfunction "DBCLK-_K10") (pintype "bidirectional"))
      (node (ref "X13") (pin "25") (pinfunction "S_25") (pintype "passive"))
    )
    (net (code "28") (name "DIFF3_P") (class "Default")
      (node (ref "IC1") (pin "K9") (pinfunction "DBCLK+_K9") (pintype "bidirectional"))
      (node (ref "X13") (pin "26") (pinfunction "S_26") (pintype "passive"))
    )
    (net (code "29") (name "DIFF4_N") (class "Default")
      (node (ref "IC1") (pin "C12") (pinfunction "DA8-_C12") (pintype "bidirectional"))
      (node (ref "X13") (pin "4") (pinfunction "S_4") (pintype "passive"))
    )
    (net (code "30") (name "DIFF4_P") (class "Default")
      (node (ref "IC1") (pin "C11") (pinfunction "DA8+_C11") (pintype "bidirectional"))
      (node (ref "X14") (pin "20") (pinfunction "S_20") (pintype "passive"))
    )
    (net (code "31") (name "DIFF5_N") (class "Default")
      (node (ref "IC1") (pin "J10") (pinfunction "DBSTR-_J10") (pintype "bidirectional"))
      (node (ref "X13") (pin "21") (pinfunction "S_21") (pintype "passive"))
    )
    (net (code "32") (name "DIFF5_P") (class "Default")
      (node (ref "IC1") (pin "J9") (pinfunction "DBSTR+_J9") (pintype "bidirectional"))
      (node (ref "X13") (pin "22") (pinfunction "S_22") (pintype "passive"))
    )
    (net (code "33") (name "DIFF6_N") (class "Default")
      (node (ref "IC1") (pin "B10") (pinfunction "DA1-_B10") (pintype "bidirectional"))
      (node (ref "X13") (pin "19") (pinfunction "S_19") (pintype "passive"))
    )
    (net (code "34") (name "DIFF6_P") (class "Default")
      (node (ref "IC1") (pin "B9") (pinfunction "DA1+_B9") (pintype "bidirectional"))
      (node (ref "X13") (pin "20") (pinfunction "S_20") (pintype "passive"))
    )
    (net (code "35") (name "DIFF7_N") (class "Default")
      (node (ref "IC1") (pin "B12") (pinfunction "DA7-_B12") (pintype "bidirectional"))
      (node (ref "X13") (pin "17") (pinfunction "S_17") (pintype "passive"))
    )
    (net (code "36") (name "DIFF7_P") (class "Default")
      (node (ref "IC1") (pin "B11") (pinfunction "DA7+_B11") (pintype "bidirectional"))
      (node (ref "X13") (pin "18") (pinfunction "S_18") (pintype "passive"))
    )
    (net (code "37") (name "DIFF8_N") (class "Default")
      (node (ref "IC1") (pin "B14") (pinfunction "DC1-_B14") (pintype "bidirectional"))
      (node (ref "X13") (pin "15") (pinfunction "S_15") (pintype "passive"))
    )
    (net (code "38") (name "DIFF8_P") (class "Default")
      (node (ref "IC1") (pin "B13") (pinfunction "DC1+_B13") (pintype "bidirectional"))
      (node (ref "X13") (pin "16") (pinfunction "S_16") (pintype "passive"))
    )
    (net (code "39") (name "DIFF9_N") (class "Default")
      (node (ref "IC1") (pin "C14") (pinfunction "DC2-_C14") (pintype "bidirectional"))
      (node (ref "X13") (pin "10") (pinfunction "S_10") (pintype "passive"))
    )
    (net (code "40") (name "DIFF9_P") (class "Default")
      (node (ref "IC1") (pin "C13") (pinfunction "DC2+_C13") (pintype "bidirectional"))
      (node (ref "X13") (pin "9") (pinfunction "S_9") (pintype "passive"))
    )
    (net (code "41") (name "DIFF10_N") (class "Default")
      (node (ref "IC1") (pin "F14") (pinfunction "DC5-_F14") (pintype "bidirectional"))
      (node (ref "X15") (pin "7") (pinfunction "S_7") (pintype "passive"))
    )
    (net (code "42") (name "DIFF10_P") (class "Default")
      (node (ref "IC1") (pin "F13") (pinfunction "DC5+_F13") (pintype "bidirectional"))
      (node (ref "X15") (pin "6") (pinfunction "S_6") (pintype "passive"))
    )
    (net (code "43") (name "DIFF11_N") (class "Default")
      (node (ref "IC1") (pin "C10") (pinfunction "DA2-_C10") (pintype "bidirectional"))
      (node (ref "X13") (pin "8") (pinfunction "S_8") (pintype "passive"))
    )
    (net (code "44") (name "DIFF11_P") (class "Default")
      (node (ref "IC1") (pin "C9") (pinfunction "DA2+_C9") (pintype "bidirectional"))
      (node (ref "X13") (pin "7") (pinfunction "S_7") (pintype "passive"))
    )
    (net (code "45") (name "DIFF12_N") (class "Default")
      (node (ref "IC1") (pin "E10") (pinfunction "DA4-_E10") (pintype "bidirectional"))
      (node (ref "X15") (pin "11") (pinfunction "S_11") (pintype "passive"))
    )
    (net (code "46") (name "DIFF12_P") (class "Default")
      (node (ref "IC1") (pin "E9") (pinfunction "DA4+_E9") (pintype "bidirectional"))
      (node (ref "X15") (pin "14") (pinfunction "S_14") (pintype "passive"))
    )
    (net (code "47") (name "DIFF13_N") (class "Default")
      (node (ref "IC1") (pin "G14") (pinfunction "DC6-_G14") (pintype "bidirectional"))
      (node (ref "X15") (pin "3") (pinfunction "S_3") (pintype "passive"))
    )
    (net (code "48") (name "DIFF13_P") (class "Default")
      (node (ref "IC1") (pin "G13") (pinfunction "DC6+_G13") (pintype "bidirectional"))
      (node (ref "X15") (pin "2") (pinfunction "S_2") (pintype "passive"))
    )
    (net (code "49") (name "DIFF14_N") (class "Default")
      (node (ref "IC1") (pin "K14") (pinfunction "DD6-_K14") (pintype "bidirectional"))
      (node (ref "X15") (pin "1") (pinfunction "S_1") (pintype "passive"))
    )
    (net (code "50") (name "DIFF14_P") (class "Default")
      (node (ref "IC1") (pin "K13") (pinfunction "DD6+_K13") (pintype "bidirectional"))
      (node (ref "X16") (pin "16") (pinfunction "S_16") (pintype "passive"))
    )
    (net (code "51") (name "DIFF15_N") (class "Default")
      (node (ref "IC1") (pin "A14") (pinfunction "DC0-_A14") (pintype "bidirectional"))
      (node (ref "X16") (pin "15") (pinfunction "S_15") (pintype "passive"))
    )
    (net (code "52") (name "DIFF15_P") (class "Default")
      (node (ref "IC1") (pin "A13") (pinfunction "DC0+_A13") (pintype "bidirectional"))
      (node (ref "X16") (pin "14") (pinfunction "S_14") (pintype "passive"))
    )
    (net (code "53") (name "DIFF16_N") (class "Default")
      (node (ref "IC1") (pin "D14") (pinfunction "DC3-_D14") (pintype "bidirectional"))
      (node (ref "X15") (pin "13") (pinfunction "S_13") (pintype "passive"))
    )
    (net (code "54") (name "DIFF16_P") (class "Default")
      (node (ref "IC1") (pin "D13") (pinfunction "DC3+_D13") (pintype "bidirectional"))
      (node (ref "X15") (pin "12") (pinfunction "S_12") (pintype "passive"))
    )
    (net (code "55") (name "DIFF17_N") (class "Default")
      (node (ref "IC1") (pin "D10") (pinfunction "DA3-_D10") (pintype "bidirectional"))
      (node (ref "X13") (pin "6") (pinfunction "S_6") (pintype "passive"))
    )
    (net (code "56") (name "DIFF17_P") (class "Default")
      (node (ref "IC1") (pin "D9") (pinfunction "DA3+_D9") (pintype "bidirectional"))
      (node (ref "X13") (pin "3") (pinfunction "S_3") (pintype "passive"))
    )
    (net (code "57") (name "DIFF18_N") (class "Default")
      (node (ref "IC1") (pin "A12") (pinfunction "DA6-_A12") (pintype "bidirectional"))
      (node (ref "X16") (pin "13") (pinfunction "S_13") (pintype "passive"))
    )
    (net (code "58") (name "DIFF18_P") (class "Default")
      (node (ref "IC1") (pin "A11") (pinfunction "DA6+_A11") (pintype "bidirectional"))
      (node (ref "X16") (pin "12") (pinfunction "S_12") (pintype "passive"))
    )
    (net (code "59") (name "DIFF19_N") (class "Default")
      (node (ref "IC1") (pin "A10") (pinfunction "DA0-_A10") (pintype "bidirectional"))
      (node (ref "X16") (pin "11") (pinfunction "S_11") (pintype "passive"))
    )
    (net (code "60") (name "DIFF19_P") (class "Default")
      (node (ref "IC1") (pin "A9") (pinfunction "DA0+_A9") (pintype "bidirectional"))
      (node (ref "X16") (pin "10") (pinfunction "S_10") (pintype "passive"))
    )
    (net (code "61") (name "DIFF20_N") (class "Default")
      (node (ref "IC1") (pin "E14") (pinfunction "DC4-_E14") (pintype "bidirectional"))
      (node (ref "X15") (pin "9") (pinfunction "S_9") (pintype "passive"))
    )
    (net (code "62") (name "DIFF20_P") (class "Default")
      (node (ref "IC1") (pin "E13") (pinfunction "DC4+_E13") (pintype "bidirectional"))
      (node (ref "X15") (pin "10") (pinfunction "S_10") (pintype "passive"))
    )
    (net (code "63") (name "DIFF21_N") (class "Default")
      (node (ref "IC1") (pin "F10") (pinfunction "DA5-_F10") (pintype "bidirectional"))
      (node (ref "X16") (pin "5") (pinfunction "S_5") (pintype "passive"))
    )
    (net (code "64") (name "DIFF21_P") (class "Default")
      (node (ref "IC1") (pin "F9") (pinfunction "DA5+_F9") (pintype "bidirectional"))
      (node (ref "X15") (pin "8") (pinfunction "S_8") (pintype "passive"))
    )
    (net (code "65") (name "DIFF22_N") (class "Default")
      (node (ref "IC1") (pin "L14") (pinfunction "DD5-_L14") (pintype "bidirectional"))
      (node (ref "X16") (pin "9") (pinfunction "S_9") (pintype "passive"))
    )
    (net (code "66") (name "DIFF22_P") (class "Default")
      (node (ref "IC1") (pin "L13") (pinfunction "DD5+_L13") (pintype "bidirectional"))
      (node (ref "X16") (pin "8") (pinfunction "S_8") (pintype "passive"))
    )
    (net (code "67") (name "DIFF23_N") (class "Default")
      (node (ref "IC1") (pin "M14") (pinfunction "DD4-_M14") (pintype "bidirectional"))
      (node (ref "X16") (pin "7") (pinfunction "S_7") (pintype "passive"))
    )
    (net (code "68") (name "DIFF23_P") (class "Default")
      (node (ref "IC1") (pin "M13") (pinfunction "DD4+_M13") (pintype "bidirectional"))
      (node (ref "X16") (pin "2") (pinfunction "S_2") (pintype "passive"))
    )
    (net (code "69") (name "DIFF24_N") (class "Default")
      (node (ref "IC1") (pin "B16") (pinfunction "DC7-_B16") (pintype "bidirectional"))
      (node (ref "X18") (pin "4") (pinfunction "S_4") (pintype "passive"))
    )
    (net (code "70") (name "DIFF24_P") (class "Default")
      (node (ref "IC1") (pin "B15") (pinfunction "DC7+_B15") (pintype "bidirectional"))
      (node (ref "X18") (pin "3") (pinfunction "S_3") (pintype "passive"))
    )
    (net (code "71") (name "DIFF25_N") (class "Default")
      (node (ref "IC1") (pin "P14") (pinfunction "DD2-_P14") (pintype "bidirectional"))
      (node (ref "X18") (pin "28") (pinfunction "S_28") (pintype "passive"))
    )
    (net (code "72") (name "DIFF25_P") (class "Default")
      (node (ref "IC1") (pin "P13") (pinfunction "DD2+_P13") (pintype "bidirectional"))
      (node (ref "X17") (pin "16") (pinfunction "S_16") (pintype "passive"))
    )
    (net (code "73") (name "DIFF26_N") (class "Default")
      (node (ref "IC1") (pin "C16") (pinfunction "DC8-_C16") (pintype "bidirectional"))
      (node (ref "X18") (pin "6") (pinfunction "S_6") (pintype "passive"))
    )
    (net (code "74") (name "DIFF26_P") (class "Default")
      (node (ref "IC1") (pin "C15") (pinfunction "DC8+_C15") (pintype "bidirectional"))
      (node (ref "X18") (pin "5") (pinfunction "S_5") (pintype "passive"))
    )
    (net (code "75") (name "DIFF27_N") (class "Default")
      (node (ref "IC1") (pin "D12") (pinfunction "DA9-_D12") (pintype "bidirectional"))
      (node (ref "X18") (pin "10") (pinfunction "S_10") (pintype "passive"))
    )
    (net (code "76") (name "DIFF27_P") (class "Default")
      (node (ref "IC1") (pin "D11") (pinfunction "DA9+_D11") (pintype "bidirectional"))
      (node (ref "X18") (pin "8") (pinfunction "S_8") (pintype "passive"))
    )
    (net (code "77") (name "DIFF28_N") (class "Default")
      (node (ref "IC1") (pin "J16") (pinfunction "DDSTR-_J16") (pintype "bidirectional"))
      (node (ref "X17") (pin "9") (pinfunction "S_9") (pintype "passive"))
    )
    (net (code "78") (name "DIFF28_P") (class "Default")
      (node (ref "IC1") (pin "J15") (pinfunction "DDSTR+_J15") (pintype "bidirectional"))
      (node (ref "X17") (pin "4") (pinfunction "S_4") (pintype "passive"))
    )
    (net (code "79") (name "DIFF29_N") (class "Default")
      (node (ref "IC1") (pin "N14") (pinfunction "DD3-_N14") (pintype "bidirectional"))
      (node (ref "X16") (pin "1") (pinfunction "S_1") (pintype "passive"))
    )
    (net (code "80") (name "DIFF29_P") (class "Default")
      (node (ref "IC1") (pin "N13") (pinfunction "DD3+_N13") (pintype "bidirectional"))
      (node (ref "X17") (pin "2") (pinfunction "S_2") (pintype "passive"))
    )
    (net (code "81") (name "DIFF30_N") (class "Default")
      (node (ref "IC1") (pin "D16") (pinfunction "DC9-_D16") (pintype "bidirectional"))
      (node (ref "X18") (pin "11") (pinfunction "S_11") (pintype "passive"))
    )
    (net (code "82") (name "DIFF30_P") (class "Default")
      (node (ref "IC1") (pin "D15") (pinfunction "DC9+_D15") (pintype "bidirectional"))
      (node (ref "X18") (pin "9") (pinfunction "S_9") (pintype "passive"))
    )
    (net (code "83") (name "DIFF31_N") (class "Default")
      (node (ref "IC1") (pin "E16") (pinfunction "DC10-_E16") (pintype "bidirectional"))
      (node (ref "X18") (pin "13") (pinfunction "S_13") (pintype "passive"))
    )
    (net (code "84") (name "DIFF31_P") (class "Default")
      (node (ref "IC1") (pin "E15") (pinfunction "DC10+_E15") (pintype "bidirectional"))
      (node (ref "X18") (pin "14") (pinfunction "S_14") (pintype "passive"))
    )
    (net (code "85") (name "DIFF32_N") (class "Default")
      (node (ref "IC1") (pin "G10") (pinfunction "DACLK-_G10") (pintype "bidirectional"))
      (node (ref "X18") (pin "15") (pinfunction "S_15") (pintype "passive"))
    )
    (net (code "86") (name "DIFF32_P") (class "Default")
      (node (ref "IC1") (pin "G9") (pinfunction "DACLK+_G9") (pintype "bidirectional"))
      (node (ref "X18") (pin "16") (pinfunction "S_16") (pintype "passive"))
    )
    (net (code "87") (name "DIFF33_N") (class "Default")
      (node (ref "IC1") (pin "H10") (pinfunction "DASTR-_H10") (pintype "bidirectional"))
      (node (ref "X18") (pin "17") (pinfunction "S_17") (pintype "passive"))
    )
    (net (code "88") (name "DIFF33_P") (class "Default")
      (node (ref "IC1") (pin "H9") (pinfunction "DASTR+_H9") (pintype "bidirectional"))
      (node (ref "X18") (pin "18") (pinfunction "S_18") (pintype "passive"))
    )
    (net (code "89") (name "DIFF34_N") (class "Default")
      (node (ref "IC1") (pin "F16") (pinfunction "DC11-_F16") (pintype "bidirectional"))
      (node (ref "X18") (pin "19") (pinfunction "S_19") (pintype "passive"))
    )
    (net (code "90") (name "DIFF34_P") (class "Default")
      (node (ref "IC1") (pin "F15") (pinfunction "DC11+_F15") (pintype "bidirectional"))
      (node (ref "X18") (pin "20") (pinfunction "S_20") (pintype "passive"))
    )
    (net (code "91") (name "DIFF35_N") (class "Default")
      (node (ref "IC1") (pin "K16") (pinfunction "DDCLK-_K16") (pintype "bidirectional"))
      (node (ref "X17") (pin "18") (pinfunction "S_18") (pintype "passive"))
    )
    (net (code "92") (name "DIFF35_P") (class "Default")
      (node (ref "IC1") (pin "K15") (pinfunction "DDCLK+_K15") (pintype "bidirectional"))
      (node (ref "X17") (pin "11") (pinfunction "S_11") (pintype "passive"))
    )
    (net (code "93") (name "DIFF36_N") (class "Default")
      (node (ref "IC1") (pin "G16") (pinfunction "DCCLK-_G16") (pintype "bidirectional"))
      (node (ref "X18") (pin "22") (pinfunction "S_22") (pintype "passive"))
    )
    (net (code "94") (name "DIFF36_P") (class "Default")
      (node (ref "IC1") (pin "G15") (pinfunction "DCCLK+_G15") (pintype "bidirectional"))
      (node (ref "X18") (pin "21") (pinfunction "S_21") (pintype "passive"))
    )
    (net (code "95") (name "DIFF37_N") (class "Default")
      (node (ref "IC1") (pin "H16") (pinfunction "DCSTR-_H16") (pintype "bidirectional"))
      (node (ref "X18") (pin "26") (pinfunction "S_26") (pintype "passive"))
    )
    (net (code "96") (name "DIFF37_P") (class "Default")
      (node (ref "IC1") (pin "H15") (pinfunction "DCSTR+_H15") (pintype "bidirectional"))
      (node (ref "X18") (pin "25") (pinfunction "S_25") (pintype "passive"))
    )
    (net (code "97") (name "DIFF38_N") (class "Default")
      (node (ref "IC1") (pin "L16") (pinfunction "DD11-_L16") (pintype "bidirectional"))
      (node (ref "X17") (pin "19") (pinfunction "S_19") (pintype "passive"))
    )
    (net (code "98") (name "DIFF38_P") (class "Default")
      (node (ref "IC1") (pin "L15") (pinfunction "DD11+_L15") (pintype "bidirectional"))
      (node (ref "X17") (pin "22") (pinfunction "S_22") (pintype "passive"))
    )
    (net (code "99") (name "DIFF39_N") (class "Default")
      (node (ref "IC1") (pin "M16") (pinfunction "DD10-_M16") (pintype "bidirectional"))
      (node (ref "X17") (pin "21") (pinfunction "S_21") (pintype "passive"))
    )
    (net (code "100") (name "DIFF39_P") (class "Default")
      (node (ref "IC1") (pin "M15") (pinfunction "DD10+_M15") (pintype "bidirectional"))
      (node (ref "X17") (pin "24") (pinfunction "S_24") (pintype "passive"))
    )
    (net (code "101") (name "DIFF40_N") (class "Default")
      (node (ref "IC1") (pin "N16") (pinfunction "DD9-_N16") (pintype "bidirectional"))
      (node (ref "X17") (pin "26") (pinfunction "S_26") (pintype "passive"))
    )
    (net (code "102") (name "DIFF40_P") (class "Default")
      (node (ref "IC1") (pin "N15") (pinfunction "DD9+_N15") (pintype "bidirectional"))
      (node (ref "X17") (pin "23") (pinfunction "S_23") (pintype "passive"))
    )
    (net (code "103") (name "DIFF41_N") (class "Default")
      (node (ref "IC1") (pin "P12") (pinfunction "DB8-_P12") (pintype "bidirectional"))
      (node (ref "X1") (pin "8") (pinfunction "S_8") (pintype "passive"))
    )
    (net (code "104") (name "DIFF41_P") (class "Default")
      (node (ref "IC1") (pin "P11") (pinfunction "DB8+_P11") (pintype "bidirectional"))
      (node (ref "X1") (pin "5") (pinfunction "S_5") (pintype "passive"))
    )
    (net (code "105") (name "DIFF42_N") (class "Default")
      (node (ref "IC1") (pin "N12") (pinfunction "DB9-_N12") (pintype "bidirectional"))
      (node (ref "X1") (pin "10") (pinfunction "S_10") (pintype "passive"))
    )
    (net (code "106") (name "DIFF42_P") (class "Default")
      (node (ref "IC1") (pin "N11") (pinfunction "DB9+_N11") (pintype "bidirectional"))
      (node (ref "X1") (pin "7") (pinfunction "S_7") (pintype "passive"))
    )
    (net (code "107") (name "DIFF43_N") (class "Default")
      (node (ref "IC1") (pin "M12") (pinfunction "DB10-_M12") (pintype "bidirectional"))
      (node (ref "X1") (pin "9") (pinfunction "S_9") (pintype "passive"))
    )
    (net (code "108") (name "DIFF43_P") (class "Default")
      (node (ref "IC1") (pin "M11") (pinfunction "DB10+_M11") (pintype "bidirectional"))
      (node (ref "X1") (pin "12") (pinfunction "S_12") (pintype "passive"))
    )
    (net (code "109") (name "DIFF44_N") (class "Default")
      (node (ref "IC1") (pin "F12") (pinfunction "DA11-_F12") (pintype "bidirectional"))
      (node (ref "X1") (pin "3") (pinfunction "S_3") (pintype "passive"))
    )
    (net (code "110") (name "DIFF44_P") (class "Default")
      (node (ref "IC1") (pin "F11") (pinfunction "DA11+_F11") (pintype "bidirectional"))
      (node (ref "X2") (pin "3") (pinfunction "S_3") (pintype "passive"))
    )
    (net (code "111") (name "DIFF45_N") (class "Default")
      (node (ref "IC1") (pin "E12") (pinfunction "DA10-_E12") (pintype "bidirectional"))
      (node (ref "X17") (pin "15") (pinfunction "S_15") (pintype "passive"))
    )
    (net (code "112") (name "DIFF45_P") (class "Default")
      (node (ref "IC1") (pin "E11") (pinfunction "DA10+_E11") (pintype "bidirectional"))
      (node (ref "X17") (pin "25") (pinfunction "S_25") (pintype "passive"))
    )
    (net (code "113") (name "DIFF46_N") (class "Default")
      (node (ref "IC1") (pin "P16") (pinfunction "DD8-_P16") (pintype "bidirectional"))
      (node (ref "X1") (pin "13") (pinfunction "S_13") (pintype "passive"))
    )
    (net (code "114") (name "DIFF46_P") (class "Default")
      (node (ref "IC1") (pin "P15") (pinfunction "DD8+_P15") (pintype "bidirectional"))
      (node (ref "X1") (pin "14") (pinfunction "S_14") (pintype "passive"))
    )
    (net (code "115") (name "DIFF47_N") (class "Default")
      (node (ref "IC1") (pin "T14") (pinfunction "DD0-_T14") (pintype "bidirectional"))
      (node (ref "X2") (pin "11") (pinfunction "S_11") (pintype "passive"))
    )
    (net (code "116") (name "DIFF47_P") (class "Default")
      (node (ref "IC1") (pin "T13") (pinfunction "DD0+_T13") (pintype "bidirectional"))
      (node (ref "X2") (pin "12") (pinfunction "S_12") (pintype "passive"))
    )
    (net (code "117") (name "DIFF48_N") (class "Default")
      (node (ref "IC1") (pin "T12") (pinfunction "DB6-_T12") (pintype "bidirectional"))
      (node (ref "X2") (pin "13") (pinfunction "S_13") (pintype "passive"))
    )
    (net (code "118") (name "DIFF48_P") (class "Default")
      (node (ref "IC1") (pin "T11") (pinfunction "DB6+_T11") (pintype "bidirectional"))
      (node (ref "X2") (pin "14") (pinfunction "S_14") (pintype "passive"))
    )
    (net (code "119") (name "DIFF49_N") (class "Default")
      (node (ref "IC1") (pin "L12") (pinfunction "DB11-_L12") (pintype "bidirectional"))
      (node (ref "X2") (pin "6") (pinfunction "S_6") (pintype "passive"))
    )
    (net (code "120") (name "DIFF49_P") (class "Default")
      (node (ref "IC1") (pin "L11") (pinfunction "DB11+_L11") (pintype "bidirectional"))
      (node (ref "X2") (pin "5") (pinfunction "S_5") (pintype "passive"))
    )
    (net (code "121") (name "DIFF50_N") (class "Default")
      (node (ref "IC1") (pin "T10") (pinfunction "DB0-_T10") (pintype "bidirectional"))
      (node (ref "X14") (pin "26") (pinfunction "S_26") (pintype "passive"))
    )
    (net (code "122") (name "DIFF50_P") (class "Default")
      (node (ref "IC1") (pin "T9") (pinfunction "DB0+_T9") (pintype "bidirectional"))
      (node (ref "X14") (pin "24") (pinfunction "S_24") (pintype "passive"))
    )
    (net (code "123") (name "DIFF51_N") (class "Default")
      (node (ref "IC1") (pin "R12") (pinfunction "DB7-_R12") (pintype "bidirectional"))
      (node (ref "X14") (pin "13") (pinfunction "S_13") (pintype "passive"))
    )
    (net (code "124") (name "DIFF51_P") (class "Default")
      (node (ref "IC1") (pin "R11") (pinfunction "DB7+_R11") (pintype "bidirectional"))
      (node (ref "X14") (pin "14") (pinfunction "S_14") (pintype "passive"))
    )
    (net (code "125") (name "DIFF52_N") (class "Default")
      (node (ref "IC1") (pin "P10") (pinfunction "DB2-_P10") (pintype "bidirectional"))
      (node (ref "X14") (pin "5") (pinfunction "S_5") (pintype "passive"))
    )
    (net (code "126") (name "DIFF52_P") (class "Default")
      (node (ref "IC1") (pin "P9") (pinfunction "DB2+_P9") (pintype "bidirectional"))
      (node (ref "X14") (pin "12") (pinfunction "S_12") (pintype "passive"))
    )
    (net (code "127") (name "DIFF53_N") (class "Default")
      (node (ref "IC1") (pin "N10") (pinfunction "DB3-_N10") (pintype "bidirectional"))
      (node (ref "X14") (pin "9") (pinfunction "S_9") (pintype "passive"))
    )
    (net (code "128") (name "DIFF53_P") (class "Default")
      (node (ref "IC1") (pin "N9") (pinfunction "DB3+_N9") (pintype "bidirectional"))
      (node (ref "X14") (pin "10") (pinfunction "S_10") (pintype "passive"))
    )
    (net (code "129") (name "DIFF54_N") (class "Default")
      (node (ref "IC1") (pin "R16") (pinfunction "DD7-_R16") (pintype "bidirectional"))
      (node (ref "X2") (pin "10") (pinfunction "S_10") (pintype "passive"))
    )
    (net (code "130") (name "DIFF54_P") (class "Default")
      (node (ref "IC1") (pin "R15") (pinfunction "DD7+_R15") (pintype "bidirectional"))
      (node (ref "X2") (pin "8") (pinfunction "S_8") (pintype "passive"))
    )
    (net (code "131") (name "DIFF55_N") (class "Default")
      (node (ref "IC1") (pin "R10") (pinfunction "DB1-_R10") (pintype "bidirectional"))
      (node (ref "X14") (pin "7") (pinfunction "S_7") (pintype "passive"))
    )
    (net (code "132") (name "DIFF55_P") (class "Default")
      (node (ref "IC1") (pin "R9") (pinfunction "DB1+_R9") (pintype "bidirectional"))
      (node (ref "X14") (pin "8") (pinfunction "S_8") (pintype "passive"))
    )
    (net (code "133") (name "DIFF56_N") (class "Default")
      (node (ref "IC1") (pin "R14") (pinfunction "DD1-_R14") (pintype "bidirectional"))
      (node (ref "X14") (pin "18") (pinfunction "S_18") (pintype "passive"))
    )
    (net (code "134") (name "DIFF56_P") (class "Default")
      (node (ref "IC1") (pin "R13") (pinfunction "DD1+_R13") (pintype "bidirectional"))
      (node (ref "X14") (pin "15") (pinfunction "S_15") (pintype "passive"))
    )
    (net (code "135") (name "E5") (class "Default")
      (node (ref "PINOUT2") (pin "6") (pinfunction "6_6") (pintype "bidirectional"))
      (node (ref "X14") (pin "25") (pinfunction "S_25") (pintype "passive"))
    )
    (net (code "136") (name "E6") (class "Default")
      (node (ref "PINOUT2") (pin "5") (pinfunction "5_5") (pintype "bidirectional"))
      (node (ref "X2") (pin "15") (pinfunction "S_15") (pintype "passive"))
    )
    (net (code "137") (name "E7") (class "Default")
      (node (ref "PINOUT2") (pin "4") (pinfunction "4_4") (pintype "bidirectional"))
      (node (ref "X2") (pin "7") (pinfunction "S_7") (pintype "passive"))
    )
    (net (code "138") (name "E9") (class "Default")
      (node (ref "PINOUT2") (pin "3") (pinfunction "3_3") (pintype "bidirectional"))
      (node (ref "X2") (pin "2") (pinfunction "S_2") (pintype "passive"))
    )
    (net (code "139") (name "E10") (class "Default")
      (node (ref "PINOUT2") (pin "7") (pinfunction "7_7") (pintype "bidirectional"))
      (node (ref "X2") (pin "1") (pinfunction "S_1") (pintype "passive"))
    )
    (net (code "140") (name "E11_SYNCSE") (class "Default")
      (node (ref "IC1") (pin "E2") (pinfunction "SYNCSE_E2") (pintype "bidirectional"))
      (node (ref "J17") (pin "1") (pinfunction "1_1") (pintype "passive"))
      (node (ref "X1") (pin "4") (pinfunction "S_4") (pintype "passive"))
    )
    (net (code "141") (name "F3") (class "Default")
      (node (ref "J8") (pin "3") (pinfunction "3_3") (pintype "passive"))
      (node (ref "R11") (pin "P$1") (pinfunction "P$1_P$1") (pintype "bidirectional"))
      (node (ref "X14") (pin "16") (pinfunction "S_16") (pintype "passive"))
    )
    (net (code "142") (name "F5") (class "Default")
      (node (ref "J10") (pin "1") (pinfunction "1_1") (pintype "passive"))
      (node (ref "R29") (pin "P$1") (pinfunction "P$1_P$1") (pintype "bidirectional"))
      (node (ref "X14") (pin "23") (pinfunction "S_23") (pintype "passive"))
    )
    (net (code "143") (name "F13") (class "Default")
      (node (ref "J8") (pin "1") (pinfunction "1_1") (pintype "passive"))
      (node (ref "R13") (pin "P$1") (pinfunction "P$1_P$1") (pintype "bidirectional"))
      (node (ref "X17") (pin "17") (pinfunction "S_17") (pintype "passive"))
    )
    (net (code "144") (name "F14") (class "Default")
      (node (ref "J8") (pin "2") (pinfunction "2_2") (pintype "passive"))
      (node (ref "R12") (pin "P$1") (pinfunction "P$1_P$1") (pintype "bidirectional"))
      (node (ref "X17") (pin "20") (pinfunction "S_20") (pintype "passive"))
    )
    (net (code "145") (name "G5") (class "Default")
      (node (ref "J8") (pin "5") (pinfunction "5_5") (pintype "passive"))
      (node (ref "R9") (pin "P$1") (pinfunction "P$1_P$1") (pintype "bidirectional"))
      (node (ref "X14") (pin "21") (pinfunction "S_21") (pintype "passive"))
    )
    (net (code "146") (name "G11") (class "Default")
      (node (ref "J8") (pin "4") (pinfunction "4_4") (pintype "passive"))
      (node (ref "R10") (pin "P$1") (pinfunction "P$1_P$1") (pintype "bidirectional"))
      (node (ref "X2") (pin "4") (pinfunction "S_4") (pintype "passive"))
    )
    (net (code "147") (name "GND") (class "Default")
      (node (ref "A14_CLKOUT2-") (pin "2") (pinfunction "2_2") (pintype "passive"))
      (node (ref "A14_CLKOUT2-") (pin "3") (pinfunction "2_3") (pintype "passive"))
      (node (ref "A14_CLKOUT2-") (pin "4") (pinfunction "2_4") (pintype "passive"))
      (node (ref "A14_CLKOUT2-") (pin "5") (pinfunction "2_5") (pintype "passive"))
      (node (ref "B14_CLKOUT2+") (pin "2") (pinfunction "2_2") (pintype "passive"))
      (node (ref "B14_CLKOUT2+") (pin "3") (pinfunction "2_3") (pintype "passive"))
      (node (ref "B14_CLKOUT2+") (pin "4") (pinfunction "2_4") (pintype "passive"))
      (node (ref "B14_CLKOUT2+") (pin "5") (pinfunction "2_5") (pintype "passive"))
      (node (ref "C10") (pin "1") (pinfunction "1_1") (pintype "passive"))
      (node (ref "C11") (pin "1") (pinfunction "1_1") (pintype "passive"))
      (node (ref "C12") (pin "1") (pinfunction "1_1") (pintype "passive"))
      (node (ref "C13") (pin "1") (pinfunction "1_1") (pintype "passive"))
      (node (ref "C14") (pin "1") (pinfunction "1_1") (pintype "passive"))
      (node (ref "C15") (pin "2") (pinfunction "GND_1_2") (pintype "bidirectional"))
      (node (ref "C15") (pin "4") (pinfunction "GND_2_4") (pintype "bidirectional"))
      (node (ref "C16") (pin "1") (pinfunction "1_1") (pintype "passive"))
      (node (ref "C17") (pin "1") (pinfunction "1_1") (pintype "passive"))
      (node (ref "C18") (pin "1") (pinfunction "1_1") (pintype "passive"))
      (node (ref "C19") (pin "1") (pinfunction "1_1") (pintype "passive"))
      (node (ref "C20") (pin "1") (pinfunction "1_1") (pintype "passive"))
      (node (ref "C21") (pin "1") (pinfunction "1_1") (pintype "passive"))
      (node (ref "C22") (pin "1") (pinfunction "1_1") (pintype "passive"))
      (node (ref "C23") (pin "1") (pinfunction "1_1") (pintype "passive"))
      (node (ref "C24") (pin "1") (pinfunction "1_1") (pintype "passive"))
      (node (ref "C25") (pin "2") (pinfunction "GND_1_2") (pintype "bidirectional"))
      (node (ref "C25") (pin "4") (pinfunction "GND_2_4") (pintype "bidirectional"))
      (node (ref "C26") (pin "1") (pinfunction "1_1") (pintype "passive"))
      (node (ref "C27") (pin "1") (pinfunction "1_1") (pintype "passive"))
      (node (ref "C28") (pin "1") (pinfunction "1_1") (pintype "passive"))
      (node (ref "C29") (pin "1") (pinfunction "1_1") (pintype "passive"))
      (node (ref "C3") (pin "1") (pinfunction "1_1") (pintype "passive"))
      (node (ref "C30") (pin "1") (pinfunction "1_1") (pintype "passive"))
      (node (ref "C31") (pin "1") (pinfunction "1_1") (pintype "passive"))
      (node (ref "C32") (pin "1") (pinfunction "1_1") (pintype "passive"))
      (node (ref "C33") (pin "1") (pinfunction "1_1") (pintype "passive"))
      (node (ref "C35") (pin "2") (pinfunction "GND_1_2") (pintype "bidirectional"))
      (node (ref "C35") (pin "4") (pinfunction "GND_2_4") (pintype "bidirectional"))
      (node (ref "C36") (pin "1") (pinfunction "1_1") (pintype "passive"))
      (node (ref "C37") (pin "1") (pinfunction "1_1") (pintype "passive"))
      (node (ref "C38") (pin "1") (pinfunction "1_1") (pintype "passive"))
      (node (ref "C39") (pin "1") (pinfunction "1_1") (pintype "passive"))
      (node (ref "C4") (pin "1") (pinfunction "1_1") (pintype "passive"))
      (node (ref "C45") (pin "2") (pinfunction "GND_1_2") (pintype "bidirectional"))
      (node (ref "C45") (pin "4") (pinfunction "GND_2_4") (pintype "bidirectional"))
      (node (ref "C46") (pin "1") (pinfunction "1_1") (pintype "passive"))
      (node (ref "C47") (pin "1") (pinfunction "1_1") (pintype "passive"))
      (node (ref "C48") (pin "1") (pinfunction "1_1") (pintype "passive"))
      (node (ref "C49") (pin "1") (pinfunction "1_1") (pintype "passive"))
      (node (ref "C5") (pin "2") (pinfunction "GND_1_2") (pintype "bidirectional"))
      (node (ref "C5") (pin "4") (pinfunction "GND_2_4") (pintype "bidirectional"))
      (node (ref "C6") (pin "1") (pinfunction "1_1") (pintype "passive"))
      (node (ref "C7") (pin "1") (pinfunction "1_1") (pintype "passive"))
      (node (ref "C8") (pin "1") (pinfunction "1_1") (pintype "passive"))
      (node (ref "C9") (pin "1") (pinfunction "1_1") (pintype "passive"))
      (node (ref "CLK+") (pin "2") (pinfunction "2_2") (pintype "passive"))
      (node (ref "CLK+") (pin "3") (pinfunction "2_3") (pintype "passive"))
      (node (ref "CLK+") (pin "4") (pinfunction "2_4") (pintype "passive"))
      (node (ref "CLK+") (pin "5") (pinfunction "2_5") (pintype "passive"))
      (node (ref "CLK-") (pin "2") (pinfunction "2_2") (pintype "passive"))
      (node (ref "CLK-") (pin "3") (pinfunction "2_3") (pintype "passive"))
      (node (ref "CLK-") (pin "4") (pinfunction "2_4") (pintype "passive"))
      (node (ref "CLK-") (pin "5") (pinfunction "2_5") (pintype "passive"))
      (node (ref "IC1") (pin "A1") (pinfunction "AGND_1_A1") (pintype "bidirectional"))
      (node (ref "IC1") (pin "A15") (pinfunction "DGND_1_A15") (pintype "bidirectional"))
      (node (ref "IC1") (pin "A16") (pinfunction "DGND_2_A16") (pintype "bidirectional"))
      (node (ref "IC1") (pin "A2") (pinfunction "AGND_2_A2") (pintype "bidirectional"))
      (node (ref "IC1") (pin "A3") (pinfunction "AGND_3_A3") (pintype "bidirectional"))
      (node (ref "IC1") (pin "A6") (pinfunction "AGND_4_A6") (pintype "bidirectional"))
      (node (ref "IC1") (pin "A7") (pinfunction "AGND_5_A7") (pintype "bidirectional"))
      (node (ref "IC1") (pin "B3") (pinfunction "AGND_6_B3") (pintype "bidirectional"))
      (node (ref "IC1") (pin "B4") (pinfunction "AGND_7_B4") (pintype "bidirectional"))
      (node (ref "IC1") (pin "B5") (pinfunction "AGND_8_B5") (pintype "bidirectional"))
      (node (ref "IC1") (pin "B6") (pinfunction "AGND_9_B6") (pintype "bidirectional"))
      (node (ref "IC1") (pin "B7") (pinfunction "AGND_10_B7") (pintype "bidirectional"))
      (node (ref "IC1") (pin "C1") (pinfunction "AGND_11_C1") (pintype "bidirectional"))
      (node (ref "IC1") (pin "C2") (pinfunction "AGND_12_C2") (pintype "bidirectional"))
      (node (ref "IC1") (pin "C3") (pinfunction "AGND_13_C3") (pintype "bidirectional"))
      (node (ref "IC1") (pin "C4") (pinfunction "AGND_14_C4") (pintype "bidirectional"))
      (node (ref "IC1") (pin "C5") (pinfunction "AGND_15_C5") (pintype "bidirectional"))
      (node (ref "IC1") (pin "C6") (pinfunction "AGND_16_C6") (pintype "bidirectional"))
      (node (ref "IC1") (pin "C7") (pinfunction "AGND_17_C7") (pintype "bidirectional"))
      (node (ref "IC1") (pin "D3") (pinfunction "AGND_18_D3") (pintype "bidirectional"))
      (node (ref "IC1") (pin "D4") (pinfunction "AGND_19_D4") (pintype "bidirectional"))
      (node (ref "IC1") (pin "D5") (pinfunction "AGND_20_D5") (pintype "bidirectional"))
      (node (ref "IC1") (pin "D6") (pinfunction "AGND_21_D6") (pintype "bidirectional"))
      (node (ref "IC1") (pin "D7") (pinfunction "DGND_3_D7") (pintype "bidirectional"))
      (node (ref "IC1") (pin "E3") (pinfunction "AGND_22_E3") (pintype "bidirectional"))
      (node (ref "IC1") (pin "E7") (pinfunction "DGND_4_E7") (pintype "bidirectional"))
      (node (ref "IC1") (pin "F1") (pinfunction "AGND_23_F1") (pintype "bidirectional"))
      (node (ref "IC1") (pin "F2") (pinfunction "AGND_24_F2") (pintype "bidirectional"))
      (node (ref "IC1") (pin "F7") (pinfunction "DGND_5_F7") (pintype "bidirectional"))
      (node (ref "IC1") (pin "G1") (pinfunction "AGND_25_G1") (pintype "bidirectional"))
      (node (ref "IC1") (pin "G2") (pinfunction "AGND_26_G2") (pintype "bidirectional"))
      (node (ref "IC1") (pin "G7") (pinfunction "DGND_6_G7") (pintype "bidirectional"))
      (node (ref "IC1") (pin "H14") (pinfunction "DGND_9_H14") (pintype "bidirectional"))
      (node (ref "IC1") (pin "H2") (pinfunction "AGND_27_H2") (pintype "bidirectional"))
      (node (ref "IC1") (pin "H7") (pinfunction "DGND_7_H7") (pintype "bidirectional"))
      (node (ref "IC1") (pin "H8") (pinfunction "DGND_8_H8") (pintype "bidirectional"))
      (node (ref "IC1") (pin "J14") (pinfunction "DGND_12_J14") (pintype "bidirectional"))
      (node (ref "IC1") (pin "J2") (pinfunction "AGND_28_J2") (pintype "bidirectional"))
      (node (ref "IC1") (pin "J7") (pinfunction "DGND_10_J7") (pintype "bidirectional"))
      (node (ref "IC1") (pin "J8") (pinfunction "DGND_11_J8") (pintype "bidirectional"))
      (node (ref "IC1") (pin "K1") (pinfunction "AGND_29_K1") (pintype "bidirectional"))
      (node (ref "IC1") (pin "K2") (pinfunction "AGND_30_K2") (pintype "bidirectional"))
      (node (ref "IC1") (pin "K7") (pinfunction "DGND_13_K7") (pintype "bidirectional"))
      (node (ref "IC1") (pin "L1") (pinfunction "AGND_31_L1") (pintype "bidirectional"))
      (node (ref "IC1") (pin "L2") (pinfunction "AGND_32_L2") (pintype "bidirectional"))
      (node (ref "IC1") (pin "L7") (pinfunction "DGND_14_L7") (pintype "bidirectional"))
      (node (ref "IC1") (pin "M3") (pinfunction "AGND_33_M3") (pintype "bidirectional"))
      (node (ref "IC1") (pin "M7") (pinfunction "DGND_15_M7") (pintype "bidirectional"))
      (node (ref "IC1") (pin "N3") (pinfunction "AGND_34_N3") (pintype "bidirectional"))
      (node (ref "IC1") (pin "N4") (pinfunction "AGND_35_N4") (pintype "bidirectional"))
      (node (ref "IC1") (pin "N5") (pinfunction "AGND_36_N5") (pintype "bidirectional"))
      (node (ref "IC1") (pin "N6") (pinfunction "AGND_37_N6") (pintype "bidirectional"))
      (node (ref "IC1") (pin "N7") (pinfunction "DGND_16_N7") (pintype "bidirectional"))
      (node (ref "IC1") (pin "P1") (pinfunction "AGND_38_P1") (pintype "bidirectional"))
      (node (ref "IC1") (pin "P2") (pinfunction "AGND_39_P2") (pintype "bidirectional"))
      (node (ref "IC1") (pin "P3") (pinfunction "AGND_40_P3") (pintype "bidirectional"))
      (node (ref "IC1") (pin "P4") (pinfunction "AGND_41_P4") (pintype "bidirectional"))
      (node (ref "IC1") (pin "P5") (pinfunction "AGND_42_P5") (pintype "bidirectional"))
      (node (ref "IC1") (pin "P6") (pinfunction "AGND_43_P6") (pintype "bidirectional"))
      (node (ref "IC1") (pin "P7") (pinfunction "AGND_44_P7") (pintype "bidirectional"))
      (node (ref "IC1") (pin "R2") (pinfunction "AGND_45_R2") (pintype "bidirectional"))
      (node (ref "IC1") (pin "R3") (pinfunction "AGND_46_R3") (pintype "bidirectional"))
      (node (ref "IC1") (pin "R4") (pinfunction "AGND_47_R4") (pintype "bidirectional"))
      (node (ref "IC1") (pin "R5") (pinfunction "AGND_48_R5") (pintype "bidirectional"))
      (node (ref "IC1") (pin "R6") (pinfunction "AGND_49_R6") (pintype "bidirectional"))
      (node (ref "IC1") (pin "R7") (pinfunction "AGND_50_R7") (pintype "bidirectional"))
      (node (ref "IC1") (pin "T1") (pinfunction "AGND_51_T1") (pintype "bidirectional"))
      (node (ref "IC1") (pin "T15") (pinfunction "DGND_17_T15") (pintype "bidirectional"))
      (node (ref "IC1") (pin "T16") (pinfunction "DGND_18_T16") (pintype "bidirectional"))
      (node (ref "IC1") (pin "T2") (pinfunction "AGND_52_T2") (pintype "bidirectional"))
      (node (ref "IC1") (pin "T3") (pinfunction "AGND_53_T3") (pintype "bidirectional"))
      (node (ref "IC1") (pin "T6") (pinfunction "AGND_54_T6") (pintype "bidirectional"))
      (node (ref "IC1") (pin "T7") (pinfunction "AGND_55_T7") (pintype "bidirectional"))
      (node (ref "IC2") (pin "10") (pinfunction "GND_10") (pintype "bidirectional"))
      (node (ref "IC2") (pin "8") (pinfunction "DIR4_8") (pintype "bidirectional"))
      (node (ref "IC2") (pin "9") (pinfunction "~{OE}_9") (pintype "bidirectional"))
      (node (ref "INA+") (pin "2") (pinfunction "2_2") (pintype "passive"))
      (node (ref "INA+") (pin "3") (pinfunction "2_3") (pintype "passive"))
      (node (ref "INA+") (pin "4") (pinfunction "2_4") (pintype "passive"))
      (node (ref "INA+") (pin "5") (pinfunction "2_5") (pintype "passive"))
      (node (ref "INA-") (pin "2") (pinfunction "2_2") (pintype "passive"))
      (node (ref "INA-") (pin "3") (pinfunction "2_3") (pintype "passive"))
      (node (ref "INA-") (pin "4") (pinfunction "2_4") (pintype "passive"))
      (node (ref "INA-") (pin "5") (pinfunction "2_5") (pintype "passive"))
      (node (ref "INB+") (pin "2") (pinfunction "2_2") (pintype "passive"))
      (node (ref "INB+") (pin "3") (pinfunction "2_3") (pintype "passive"))
      (node (ref "INB+") (pin "4") (pinfunction "2_4") (pintype "passive"))
      (node (ref "INB+") (pin "5") (pinfunction "2_5") (pintype "passive"))
      (node (ref "INB-") (pin "2") (pinfunction "2_2") (pintype "passive"))
      (node (ref "INB-") (pin "3") (pinfunction "2_3") (pintype "passive"))
      (node (ref "INB-") (pin "4") (pinfunction "2_4") (pintype "passive"))
      (node (ref "INB-") (pin "5") (pinfunction "2_5") (pintype "passive"))
      (node (ref "J17") (pin "3") (pinfunction "3_3") (pintype "passive"))
      (node (ref "J17") (pin "7") (pinfunction "7_7") (pintype "passive"))
      (node (ref "J17") (pin "8") (pinfunction "8_8") (pintype "passive"))
      (node (ref "J2") (pin "5") (pinfunction "5_5") (pintype "passive"))
      (node (ref "J2") (pin "6") (pinfunction "6_6") (pintype "passive"))
      (node (ref "J2") (pin "7") (pinfunction "7_7") (pintype "passive"))
      (node (ref "J2") (pin "8") (pinfunction "8_8") (pintype "passive"))
      (node (ref "J4") (pin "2") (pinfunction "2_2") (pintype "passive"))
      (node (ref "J4") (pin "8") (pinfunction "8_8") (pintype "passive"))
      (node (ref "J5") (pin "1") (pinfunction "1_1") (pintype "passive"))
      (node (ref "J5") (pin "4") (pinfunction "4_4") (pintype "passive"))
      (node (ref "J5") (pin "6") (pinfunction "6_6") (pintype "passive"))
      (node (ref "J5") (pin "8") (pinfunction "8_8") (pintype "passive"))
      (node (ref "J6") (pin "1") (pinfunction "1_1") (pintype "passive"))
      (node (ref "J6") (pin "4") (pinfunction "4_4") (pintype "passive"))
      (node (ref "J6") (pin "5") (pinfunction "5_5") (pintype "passive"))
      (node (ref "J6") (pin "8") (pinfunction "8_8") (pintype "passive"))
      (node (ref "J7") (pin "3") (pinfunction "3_3") (pintype "passive"))
      (node (ref "J7") (pin "6") (pinfunction "6_6") (pintype "passive"))
      (node (ref "LED1") (pin "C") (pinfunction "C_C") (pintype "passive"))
      (node (ref "LED17") (pin "C") (pinfunction "C_C") (pintype "passive"))
      (node (ref "LED18") (pin "C") (pinfunction "C_C") (pintype "passive"))
      (node (ref "LED19") (pin "C") (pinfunction "C_C") (pintype "passive"))
      (node (ref "LED2") (pin "C") (pinfunction "C_C") (pintype "passive"))
      (node (ref "LED20") (pin "C") (pinfunction "C_C") (pintype "passive"))
      (node (ref "LED21") (pin "C") (pinfunction "C_C") (pintype "passive"))
      (node (ref "LED22") (pin "C") (pinfunction "C_C") (pintype "passive"))
      (node (ref "LED23") (pin "C") (pinfunction "C_C") (pintype "passive"))
      (node (ref "LED24") (pin "C") (pinfunction "C_C") (pintype "passive"))
      (node (ref "LED25") (pin "C") (pinfunction "C_C") (pintype "passive"))
      (node (ref "LED26") (pin "C") (pinfunction "C_C") (pintype "passive"))
      (node (ref "LED27") (pin "C") (pinfunction "C_C") (pintype "passive"))
      (node (ref "LED28") (pin "C") (pinfunction "C_C") (pintype "passive"))
      (node (ref "LED29") (pin "C") (pinfunction "C_C") (pintype "passive"))
      (node (ref "LED3") (pin "C") (pinfunction "C_C") (pintype "passive"))
      (node (ref "LED30") (pin "C") (pinfunction "C_C") (pintype "passive"))
      (node (ref "LED31") (pin "C") (pinfunction "C_C") (pintype "passive"))
      (node (ref "LED32") (pin "C") (pinfunction "C_C") (pintype "passive"))
      (node (ref "LED33") (pin "C") (pinfunction "C_C") (pintype "passive"))
      (node (ref "LED34") (pin "C") (pinfunction "C_C") (pintype "passive"))
      (node (ref "LED35") (pin "C") (pinfunction "C_C") (pintype "passive"))
      (node (ref "LED36") (pin "C") (pinfunction "C_C") (pintype "passive"))
      (node (ref "LED37") (pin "C") (pinfunction "C_C") (pintype "passive"))
      (node (ref "LED38") (pin "C") (pinfunction "C_C") (pintype "passive"))
      (node (ref "LED39") (pin "C") (pinfunction "C_C") (pintype "passive"))
      (node (ref "LED4") (pin "C") (pinfunction "C_C") (pintype "passive"))
      (node (ref "LED40") (pin "C") (pinfunction "C_C") (pintype "passive"))
      (node (ref "LED41") (pin "C") (pinfunction "C_C") (pintype "passive"))
      (node (ref "LED42") (pin "C") (pinfunction "C_C") (pintype "passive"))
      (node (ref "LED43") (pin "C") (pinfunction "C_C") (pintype "passive"))
      (node (ref "LED44") (pin "C") (pinfunction "C_C") (pintype "passive"))
      (node (ref "LED45") (pin "C") (pinfunction "C_C") (pintype "passive"))
      (node (ref "LED46") (pin "C") (pinfunction "C_C") (pintype "passive"))
      (node (ref "LED47") (pin "C") (pinfunction "C_C") (pintype "passive"))
      (node (ref "LED48") (pin "C") (pinfunction "C_C") (pintype "passive"))
      (node (ref "LED5") (pin "C") (pinfunction "C_C") (pintype "passive"))
      (node (ref "LED6") (pin "C") (pinfunction "C_C") (pintype "passive"))
      (node (ref "LED7") (pin "C") (pinfunction "C_C") (pintype "passive"))
      (node (ref "LED8") (pin "C") (pinfunction "C_C") (pintype "passive"))
      (node (ref "PINOUT1") (pin "1") (pinfunction "1_1") (pintype "bidirectional"))
      (node (ref "PINOUT2") (pin "1") (pinfunction "1_1") (pintype "bidirectional"))
      (node (ref "R4_CLKOUT+") (pin "2") (pinfunction "2_2") (pintype "passive"))
      (node (ref "R4_CLKOUT+") (pin "3") (pinfunction "2_3") (pintype "passive"))
      (node (ref "R4_CLKOUT+") (pin "4") (pinfunction "2_4") (pintype "passive"))
      (node (ref "R4_CLKOUT+") (pin "5") (pinfunction "2_5") (pintype "passive"))
      (node (ref "T4_CLKOUT-") (pin "2") (pinfunction "2_2") (pintype "passive"))
      (node (ref "T4_CLKOUT-") (pin "3") (pinfunction "2_3") (pintype "passive"))
      (node (ref "T4_CLKOUT-") (pin "4") (pinfunction "2_4") (pintype "passive"))
      (node (ref "T4_CLKOUT-") (pin "5") (pinfunction "2_5") (pintype "passive"))
      (node (ref "X13") (pin "2") (pinfunction "S_2") (pintype "passive"))
      (node (ref "X13") (pin "24") (pinfunction "S_24") (pintype "passive"))
      (node (ref "X18") (pin "1") (pinfunction "S_1") (pintype "passive"))
      (node (ref "X18") (pin "23") (pinfunction "S_23") (pintype "passive"))
    )
    (net (code "148") (name "INA_N") (class "Default")
      (node (ref "IC1") (pin "A5") (pinfunction "INA-_A5") (pintype "bidirectional"))
      (node (ref "INA-") (pin "1") (pinfunction "1_1") (pintype "passive"))
    )
    (net (code "149") (name "INA_P") (class "Default")
      (node (ref "IC1") (pin "A4") (pinfunction "INA+_A4") (pintype "bidirectional"))
      (node (ref "INA+") (pin "1") (pinfunction "1_1") (pintype "passive"))
    )
    (net (code "150") (name "INB_N") (class "Default")
      (node (ref "IC1") (pin "T5") (pinfunction "INB-_T5") (pintype "bidirectional"))
      (node (ref "INB-") (pin "1") (pinfunction "1_1") (pintype "passive"))
    )
    (net (code "151") (name "INB_P") (class "Default")
      (node (ref "IC1") (pin "T4") (pinfunction "INB+_T4") (pintype "bidirectional"))
      (node (ref "INB+") (pin "1") (pinfunction "1_1") (pintype "passive"))
    )
    (net (code "152") (name "J6") (class "Default")
      (node (ref "J8") (pin "8") (pinfunction "8_8") (pintype "passive"))
      (node (ref "R6") (pin "P$1") (pinfunction "P$1_P$1") (pintype "bidirectional"))
      (node (ref "X14") (pin "22") (pinfunction "S_22") (pintype "passive"))
    )
    (net (code "153") (name "J11") (class "Default")
      (node (ref "J8") (pin "6") (pinfunction "6_6") (pintype "passive"))
      (node (ref "R8") (pin "P$1") (pinfunction "P$1_P$1") (pintype "bidirectional"))
      (node (ref "X17") (pin "13") (pinfunction "S_13") (pintype "passive"))
    )
    (net (code "154") (name "J13") (class "Default")
      (node (ref "J8") (pin "7") (pinfunction "7_7") (pintype "passive"))
      (node (ref "R7") (pin "P$1") (pinfunction "P$1_P$1") (pintype "bidirectional"))
      (node (ref "X17") (pin "10") (pinfunction "S_10") (pintype "passive"))
    )
    (net (code "155") (name "K5") (class "Default")
      (node (ref "J10") (pin "4") (pinfunction "4_4") (pintype "passive"))
      (node (ref "R26") (pin "P$1") (pinfunction "P$1_P$1") (pintype "bidirectional"))
      (node (ref "X14") (pin "19") (pinfunction "S_19") (pintype "passive"))
    )
    (net (code "156") (name "K11") (class "Default")
      (node (ref "J10") (pin "2") (pinfunction "2_2") (pintype "passive"))
      (node (ref "R28") (pin "P$1") (pinfunction "P$1_P$1") (pintype "bidirectional"))
      (node (ref "X17") (pin "14") (pinfunction "S_14") (pintype "passive"))
    )
    (net (code "157") (name "K12") (class "Default")
      (node (ref "J10") (pin "3") (pinfunction "3_3") (pintype "passive"))
      (node (ref "R27") (pin "P$1") (pinfunction "P$1_P$1") (pintype "bidirectional"))
      (node (ref "X17") (pin "12") (pinfunction "S_12") (pintype "passive"))
    )
    (net (code "158") (name "L3") (class "Default")
      (node (ref "J10") (pin "8") (pinfunction "8_8") (pintype "passive"))
      (node (ref "R22") (pin "P$1") (pinfunction "P$1_P$1") (pintype "bidirectional"))
      (node (ref "X13") (pin "11") (pinfunction "S_11") (pintype "passive"))
    )
    (net (code "159") (name "L4") (class "Default")
      (node (ref "J11") (pin "1") (pinfunction "1_1") (pintype "passive"))
      (node (ref "R37") (pin "P$1") (pinfunction "P$1_P$1") (pintype "bidirectional"))
      (node (ref "X13") (pin "12") (pinfunction "S_12") (pintype "passive"))
    )
    (net (code "160") (name "L7") (class "Default")
      (node (ref "J11") (pin "2") (pinfunction "2_2") (pintype "passive"))
      (node (ref "R36") (pin "P$1") (pinfunction "P$1_P$1") (pintype "bidirectional"))
      (node (ref "X15") (pin "15") (pinfunction "S_15") (pintype "passive"))
    )
    (net (code "161") (name "L12") (class "Default")
      (node (ref "J10") (pin "5") (pinfunction "5_5") (pintype "passive"))
      (node (ref "R25") (pin "P$1") (pinfunction "P$1_P$1") (pintype "bidirectional"))
      (node (ref "X17") (pin "8") (pinfunction "S_8") (pintype "passive"))
    )
    (net (code "162") (name "L13") (class "Default")
      (node (ref "J10") (pin "6") (pinfunction "6_6") (pintype "passive"))
      (node (ref "R24") (pin "P$1") (pinfunction "P$1_P$1") (pintype "bidirectional"))
      (node (ref "X17") (pin "6") (pinfunction "S_6") (pintype "passive"))
    )
    (net (code "163") (name "L14") (class "Default")
      (node (ref "J10") (pin "7") (pinfunction "7_7") (pintype "passive"))
      (node (ref "R23") (pin "P$1") (pinfunction "P$1_P$1") (pintype "bidirectional"))
      (node (ref "X17") (pin "7") (pinfunction "S_7") (pintype "passive"))
    )
    (net (code "164") (name "M6") (class "Default")
      (node (ref "J11") (pin "5") (pinfunction "5_5") (pintype "passive"))
      (node (ref "R33") (pin "P$1") (pinfunction "P$1_P$1") (pintype "bidirectional"))
      (node (ref "X15") (pin "16") (pinfunction "S_16") (pintype "passive"))
    )
    (net (code "165") (name "M10") (class "Default")
      (node (ref "J11") (pin "3") (pinfunction "3_3") (pintype "passive"))
      (node (ref "R35") (pin "P$1") (pinfunction "P$1_P$1") (pintype "bidirectional"))
      (node (ref "X18") (pin "27") (pinfunction "S_27") (pintype "passive"))
    )
    (net (code "166") (name "M12") (class "Default")
      (node (ref "J11") (pin "4") (pinfunction "4_4") (pintype "passive"))
      (node (ref "R34") (pin "P$1") (pinfunction "P$1_P$1") (pintype "bidirectional"))
      (node (ref "X17") (pin "5") (pinfunction "S_5") (pintype "passive"))
    )
    (net (code "167") (name "N11") (class "Default")
      (node (ref "J11") (pin "6") (pinfunction "6_6") (pintype "passive"))
      (node (ref "R32") (pin "P$1") (pinfunction "P$1_P$1") (pintype "bidirectional"))
      (node (ref "X16") (pin "3") (pinfunction "S_3") (pintype "passive"))
    )
    (net (code "168") (name "N13") (class "Default")
      (node (ref "J11") (pin "7") (pinfunction "7_7") (pintype "passive"))
      (node (ref "R31") (pin "P$1") (pinfunction "P$1_P$1") (pintype "bidirectional"))
      (node (ref "X17") (pin "1") (pinfunction "S_1") (pintype "passive"))
    )
    (net (code "169") (name "N14") (class "Default")
      (node (ref "J11") (pin "8") (pinfunction "8_8") (pintype "passive"))
      (node (ref "R30") (pin "P$1") (pinfunction "P$1_P$1") (pintype "bidirectional"))
      (node (ref "X17") (pin "3") (pinfunction "S_3") (pintype "passive"))
    )
    (net (code "170") (name "Net-(LED1-PadA)") (class "Default")
      (node (ref "LED1") (pin "A") (pinfunction "A_A") (pintype "passive"))
      (node (ref "R13") (pin "P$2") (pinfunction "P$2_P$2") (pintype "bidirectional"))
    )
    (net (code "171") (name "Net-(LED2-PadA)") (class "Default")
      (node (ref "LED2") (pin "A") (pinfunction "A_A") (pintype "passive"))
      (node (ref "R12") (pin "P$2") (pinfunction "P$2_P$2") (pintype "bidirectional"))
    )
    (net (code "172") (name "Net-(LED3-PadA)") (class "Default")
      (node (ref "LED3") (pin "A") (pinfunction "A_A") (pintype "passive"))
      (node (ref "R11") (pin "P$2") (pinfunction "P$2_P$2") (pintype "bidirectional"))
    )
    (net (code "173") (name "Net-(LED4-PadA)") (class "Default")
      (node (ref "LED4") (pin "A") (pinfunction "A_A") (pintype "passive"))
      (node (ref "R10") (pin "P$2") (pinfunction "P$2_P$2") (pintype "bidirectional"))
    )
    (net (code "174") (name "Net-(LED5-PadA)") (class "Default")
      (node (ref "LED5") (pin "A") (pinfunction "A_A") (pintype "passive"))
      (node (ref "R9") (pin "P$2") (pinfunction "P$2_P$2") (pintype "bidirectional"))
    )
    (net (code "175") (name "Net-(LED6-PadA)") (class "Default")
      (node (ref "LED6") (pin "A") (pinfunction "A_A") (pintype "passive"))
      (node (ref "R8") (pin "P$2") (pinfunction "P$2_P$2") (pintype "bidirectional"))
    )
    (net (code "176") (name "Net-(LED7-PadA)") (class "Default")
      (node (ref "LED7") (pin "A") (pinfunction "A_A") (pintype "passive"))
      (node (ref "R7") (pin "P$2") (pinfunction "P$2_P$2") (pintype "bidirectional"))
    )
    (net (code "177") (name "Net-(LED8-PadA)") (class "Default")
      (node (ref "LED8") (pin "A") (pinfunction "A_A") (pintype "passive"))
      (node (ref "R6") (pin "P$2") (pinfunction "P$2_P$2") (pintype "bidirectional"))
    )
    (net (code "178") (name "Net-(LED17-PadA)") (class "Default")
      (node (ref "LED17") (pin "A") (pinfunction "A_A") (pintype "passive"))
      (node (ref "R29") (pin "P$2") (pinfunction "P$2_P$2") (pintype "bidirectional"))
    )
    (net (code "179") (name "Net-(LED18-PadA)") (class "Default")
      (node (ref "LED18") (pin "A") (pinfunction "A_A") (pintype "passive"))
      (node (ref "R28") (pin "P$2") (pinfunction "P$2_P$2") (pintype "bidirectional"))
    )
    (net (code "180") (name "Net-(LED19-PadA)") (class "Default")
      (node (ref "LED19") (pin "A") (pinfunction "A_A") (pintype "passive"))
      (node (ref "R27") (pin "P$2") (pinfunction "P$2_P$2") (pintype "bidirectional"))
    )
    (net (code "181") (name "Net-(LED20-PadA)") (class "Default")
      (node (ref "LED20") (pin "A") (pinfunction "A_A") (pintype "passive"))
      (node (ref "R26") (pin "P$2") (pinfunction "P$2_P$2") (pintype "bidirectional"))
    )
    (net (code "182") (name "Net-(LED21-PadA)") (class "Default")
      (node (ref "LED21") (pin "A") (pinfunction "A_A") (pintype "passive"))
      (node (ref "R25") (pin "P$2") (pinfunction "P$2_P$2") (pintype "bidirectional"))
    )
    (net (code "183") (name "Net-(LED22-PadA)") (class "Default")
      (node (ref "LED22") (pin "A") (pinfunction "A_A") (pintype "passive"))
      (node (ref "R24") (pin "P$2") (pinfunction "P$2_P$2") (pintype "bidirectional"))
    )
    (net (code "184") (name "Net-(LED23-PadA)") (class "Default")
      (node (ref "LED23") (pin "A") (pinfunction "A_A") (pintype "passive"))
      (node (ref "R23") (pin "P$2") (pinfunction "P$2_P$2") (pintype "bidirectional"))
    )
    (net (code "185") (name "Net-(LED24-PadA)") (class "Default")
      (node (ref "LED24") (pin "A") (pinfunction "A_A") (pintype "passive"))
      (node (ref "R22") (pin "P$2") (pinfunction "P$2_P$2") (pintype "bidirectional"))
    )
    (net (code "186") (name "Net-(LED25-PadA)") (class "Default")
      (node (ref "LED25") (pin "A") (pinfunction "A_A") (pintype "passive"))
      (node (ref "R37") (pin "P$2") (pinfunction "P$2_P$2") (pintype "bidirectional"))
    )
    (net (code "187") (name "Net-(LED26-PadA)") (class "Default")
      (node (ref "LED26") (pin "A") (pinfunction "A_A") (pintype "passive"))
      (node (ref "R36") (pin "P$2") (pinfunction "P$2_P$2") (pintype "bidirectional"))
    )
    (net (code "188") (name "Net-(LED27-PadA)") (class "Default")
      (node (ref "LED27") (pin "A") (pinfunction "A_A") (pintype "passive"))
      (node (ref "R35") (pin "P$2") (pinfunction "P$2_P$2") (pintype "bidirectional"))
    )
    (net (code "189") (name "Net-(LED28-PadA)") (class "Default")
      (node (ref "LED28") (pin "A") (pinfunction "A_A") (pintype "passive"))
      (node (ref "R34") (pin "P$2") (pinfunction "P$2_P$2") (pintype "bidirectional"))
    )
    (net (code "190") (name "Net-(LED29-PadA)") (class "Default")
      (node (ref "LED29") (pin "A") (pinfunction "A_A") (pintype "passive"))
      (node (ref "R33") (pin "P$2") (pinfunction "P$2_P$2") (pintype "bidirectional"))
    )
    (net (code "191") (name "Net-(LED30-PadA)") (class "Default")
      (node (ref "LED30") (pin "A") (pinfunction "A_A") (pintype "passive"))
      (node (ref "R32") (pin "P$2") (pinfunction "P$2_P$2") (pintype "bidirectional"))
    )
    (net (code "192") (name "Net-(LED31-PadA)") (class "Default")
      (node (ref "LED31") (pin "A") (pinfunction "A_A") (pintype "passive"))
      (node (ref "R31") (pin "P$2") (pinfunction "P$2_P$2") (pintype "bidirectional"))
    )
    (net (code "193") (name "Net-(LED32-PadA)") (class "Default")
      (node (ref "LED32") (pin "A") (pinfunction "A_A") (pintype "passive"))
      (node (ref "R30") (pin "P$2") (pinfunction "P$2_P$2") (pintype "bidirectional"))
    )
    (net (code "194") (name "Net-(LED33-PadA)") (class "Default")
      (node (ref "LED33") (pin "A") (pinfunction "A_A") (pintype "passive"))
      (node (ref "R45") (pin "P$2") (pinfunction "P$2_P$2") (pintype "bidirectional"))
    )
    (net (code "195") (name "Net-(LED34-PadA)") (class "Default")
      (node (ref "LED34") (pin "A") (pinfunction "A_A") (pintype "passive"))
      (node (ref "R44") (pin "P$2") (pinfunction "P$2_P$2") (pintype "bidirectional"))
    )
    (net (code "196") (name "Net-(LED35-PadA)") (class "Default")
      (node (ref "LED35") (pin "A") (pinfunction "A_A") (pintype "passive"))
      (node (ref "R43") (pin "P$2") (pinfunction "P$2_P$2") (pintype "bidirectional"))
    )
    (net (code "197") (name "Net-(LED36-PadA)") (class "Default")
      (node (ref "LED36") (pin "A") (pinfunction "A_A") (pintype "passive"))
      (node (ref "R42") (pin "P$2") (pinfunction "P$2_P$2") (pintype "bidirectional"))
    )
    (net (code "198") (name "Net-(LED37-PadA)") (class "Default")
      (node (ref "LED37") (pin "A") (pinfunction "A_A") (pintype "passive"))
      (node (ref "R41") (pin "P$2") (pinfunction "P$2_P$2") (pintype "bidirectional"))
    )
    (net (code "199") (name "Net-(LED38-PadA)") (class "Default")
      (node (ref "LED38") (pin "A") (pinfunction "A_A") (pintype "passive"))
      (node (ref "R40") (pin "P$2") (pinfunction "P$2_P$2") (pintype "bidirectional"))
    )
    (net (code "200") (name "Net-(LED39-PadA)") (class "Default")
      (node (ref "LED39") (pin "A") (pinfunction "A_A") (pintype "passive"))
      (node (ref "R39") (pin "P$2") (pinfunction "P$2_P$2") (pintype "bidirectional"))
    )
    (net (code "201") (name "Net-(LED40-PadA)") (class "Default")
      (node (ref "LED40") (pin "A") (pinfunction "A_A") (pintype "passive"))
      (node (ref "R38") (pin "P$2") (pinfunction "P$2_P$2") (pintype "bidirectional"))
    )
    (net (code "202") (name "Net-(LED41-PadA)") (class "Default")
      (node (ref "LED41") (pin "A") (pinfunction "A_A") (pintype "passive"))
      (node (ref "R53") (pin "P$2") (pinfunction "P$2_P$2") (pintype "bidirectional"))
    )
    (net (code "203") (name "Net-(LED42-PadA)") (class "Default")
      (node (ref "LED42") (pin "A") (pinfunction "A_A") (pintype "passive"))
      (node (ref "R52") (pin "P$2") (pinfunction "P$2_P$2") (pintype "bidirectional"))
    )
    (net (code "204") (name "Net-(LED43-PadA)") (class "Default")
      (node (ref "LED43") (pin "A") (pinfunction "A_A") (pintype "passive"))
      (node (ref "R51") (pin "P$2") (pinfunction "P$2_P$2") (pintype "bidirectional"))
    )
    (net (code "205") (name "Net-(LED44-PadA)") (class "Default")
      (node (ref "LED44") (pin "A") (pinfunction "A_A") (pintype "passive"))
      (node (ref "R50") (pin "P$2") (pinfunction "P$2_P$2") (pintype "bidirectional"))
    )
    (net (code "206") (name "Net-(LED45-PadA)") (class "Default")
      (node (ref "LED45") (pin "A") (pinfunction "A_A") (pintype "passive"))
      (node (ref "R49") (pin "P$2") (pinfunction "P$2_P$2") (pintype "bidirectional"))
    )
    (net (code "207") (name "Net-(LED46-PadA)") (class "Default")
      (node (ref "LED46") (pin "A") (pinfunction "A_A") (pintype "passive"))
      (node (ref "R48") (pin "P$2") (pinfunction "P$2_P$2") (pintype "bidirectional"))
    )
    (net (code "208") (name "Net-(LED47-PadA)") (class "Default")
      (node (ref "LED47") (pin "A") (pinfunction "A_A") (pintype "passive"))
      (node (ref "R47") (pin "P$2") (pinfunction "P$2_P$2") (pintype "bidirectional"))
    )
    (net (code "209") (name "Net-(LED48-PadA)") (class "Default")
      (node (ref "LED48") (pin "A") (pinfunction "A_A") (pintype "passive"))
      (node (ref "R46") (pin "P$2") (pinfunction "P$2_P$2") (pintype "bidirectional"))
    )
    (net (code "210") (name "ORA0") (class "Default")
      (node (ref "IC1") (pin "B8") (pinfunction "ORA0_B8") (pintype "bidirectional"))
      (node (ref "J12") (pin "5") (pinfunction "5_5") (pintype "passive"))
      (node (ref "J16") (pin "5") (pinfunction "5_5") (pintype "passive"))
      (node (ref "R41") (pin "P$1") (pinfunction "P$1_P$1") (pintype "bidirectional"))
    )
    (net (code "211") (name "ORA1") (class "Default")
      (node (ref "IC1") (pin "A8") (pinfunction "ORA1_A8") (pintype "bidirectional"))
      (node (ref "J12") (pin "6") (pinfunction "6_6") (pintype "passive"))
      (node (ref "J16") (pin "6") (pinfunction "6_6") (pintype "passive"))
      (node (ref "R40") (pin "P$1") (pinfunction "P$1_P$1") (pintype "bidirectional"))
    )
    (net (code "212") (name "ORB0") (class "Default")
      (node (ref "IC1") (pin "D8") (pinfunction "ORB0_D8") (pintype "bidirectional"))
      (node (ref "J12") (pin "7") (pinfunction "7_7") (pintype "passive"))
      (node (ref "J16") (pin "7") (pinfunction "7_7") (pintype "passive"))
      (node (ref "R39") (pin "P$1") (pinfunction "P$1_P$1") (pintype "bidirectional"))
    )
    (net (code "213") (name "ORB1") (class "Default")
      (node (ref "IC1") (pin "C8") (pinfunction "ORB1_C8") (pintype "bidirectional"))
      (node (ref "J12") (pin "8") (pinfunction "8_8") (pintype "passive"))
      (node (ref "J16") (pin "8") (pinfunction "8_8") (pintype "passive"))
      (node (ref "R38") (pin "P$1") (pinfunction "P$1_P$1") (pintype "bidirectional"))
    )
    (net (code "214") (name "P6") (class "Default")
      (node (ref "J13") (pin "3") (pinfunction "3_3") (pintype "passive"))
      (node (ref "R51") (pin "P$1") (pinfunction "P$1_P$1") (pintype "bidirectional"))
      (node (ref "X13") (pin "5") (pinfunction "S_5") (pintype "passive"))
    )
    (net (code "215") (name "P9") (class "Default")
      (node (ref "J13") (pin "4") (pinfunction "4_4") (pintype "passive"))
      (node (ref "R50") (pin "P$1") (pinfunction "P$1_P$1") (pintype "bidirectional"))
      (node (ref "X16") (pin "6") (pinfunction "S_6") (pintype "passive"))
    )
    (net (code "216") (name "P11") (class "Default")
      (node (ref "J13") (pin "1") (pinfunction "1_1") (pintype "passive"))
      (node (ref "R53") (pin "P$1") (pinfunction "P$1_P$1") (pintype "bidirectional"))
      (node (ref "X16") (pin "4") (pinfunction "S_4") (pintype "passive"))
    )
    (net (code "217") (name "P15") (class "Default")
      (node (ref "J13") (pin "2") (pinfunction "2_2") (pintype "passive"))
      (node (ref "R52") (pin "P$1") (pinfunction "P$1_P$1") (pintype "bidirectional"))
      (node (ref "X18") (pin "12") (pinfunction "S_12") (pintype "passive"))
    )
    (net (code "218") (name "PD") (class "Default")
      (node (ref "IC1") (pin "R1") (pinfunction "PD_R1") (pintype "bidirectional"))
      (node (ref "J17") (pin "6") (pinfunction "6_6") (pintype "passive"))
    )
    (net (code "219") (name "R1") (class "Default")
      (node (ref "J13") (pin "5") (pinfunction "5_5") (pintype "passive"))
      (node (ref "R49") (pin "P$1") (pinfunction "P$1_P$1") (pintype "bidirectional"))
      (node (ref "X13") (pin "13") (pinfunction "S_13") (pintype "passive"))
    )
    (net (code "220") (name "R4_CLKOUT1P") (class "Default")
      (node (ref "R4_CLKOUT+") (pin "1") (pinfunction "1_1") (pintype "passive"))
      (node (ref "X15") (pin "4") (pinfunction "S_4") (pintype "passive"))
    )
    (net (code "221") (name "R14") (class "Default")
      (node (ref "J13") (pin "6") (pinfunction "6_6") (pintype "passive"))
      (node (ref "R48") (pin "P$1") (pinfunction "P$1_P$1") (pintype "bidirectional"))
      (node (ref "X18") (pin "7") (pinfunction "S_7") (pintype "passive"))
    )
    (net (code "222") (name "SCLK") (class "Default")
      (node (ref "IC1") (pin "T8") (pinfunction "SCLK_T8") (pintype "bidirectional"))
      (node (ref "J16") (pin "1") (pinfunction "1_1") (pintype "passive"))
      (node (ref "R1") (pin "P$2") (pinfunction "P$2_P$2") (pintype "bidirectional"))
    )
    (net (code "223") (name "SCLK3") (class "Default")
      (node (ref "IC2") (pin "3") (pinfunction "A1_3") (pintype "bidirectional"))
      (node (ref "J4") (pin "3") (pinfunction "3_3") (pintype "passive"))
    )
    (net (code "224") (name "SCLKT") (class "Default")
      (node (ref "IC2") (pin "14") (pinfunction "B1_14") (pintype "bidirectional"))
      (node (ref "R1") (pin "P$1") (pinfunction "P$1_P$1") (pintype "bidirectional"))
    )
    (net (code "225") (name "SCS") (class "Default")
      (node (ref "IC1") (pin "R8") (pinfunction "SCS_R8") (pintype "bidirectional"))
      (node (ref "J16") (pin "2") (pinfunction "2_2") (pintype "passive"))
      (node (ref "R2") (pin "P$2") (pinfunction "P$2_P$2") (pintype "bidirectional"))
    )
    (net (code "226") (name "SCS3") (class "Default")
      (node (ref "IC2") (pin "4") (pinfunction "A2_4") (pintype "bidirectional"))
      (node (ref "J4") (pin "4") (pinfunction "4_4") (pintype "passive"))
    )
    (net (code "227") (name "SCST") (class "Default")
      (node (ref "IC2") (pin "13") (pinfunction "B2_13") (pintype "bidirectional"))
      (node (ref "R2") (pin "P$1") (pinfunction "P$1_P$1") (pintype "bidirectional"))
      (node (ref "R5") (pin "P$2") (pinfunction "P$2_P$2") (pintype "bidirectional"))
    )
    (net (code "228") (name "SDI") (class "Default")
      (node (ref "IC1") (pin "P8") (pinfunction "SDI_P8") (pintype "bidirectional"))
      (node (ref "J16") (pin "3") (pinfunction "3_3") (pintype "passive"))
      (node (ref "R3") (pin "P$2") (pinfunction "P$2_P$2") (pintype "bidirectional"))
    )
    (net (code "229") (name "SDI3") (class "Default")
      (node (ref "IC2") (pin "5") (pinfunction "A3_5") (pintype "bidirectional"))
      (node (ref "J4") (pin "5") (pinfunction "5_5") (pintype "passive"))
    )
    (net (code "230") (name "SDIT") (class "Default")
      (node (ref "IC2") (pin "12") (pinfunction "B3_12") (pintype "bidirectional"))
      (node (ref "R3") (pin "P$1") (pinfunction "P$1_P$1") (pintype "bidirectional"))
    )
    (net (code "231") (name "SDO") (class "Default")
      (node (ref "IC1") (pin "N8") (pinfunction "SDO_N8") (pintype "bidirectional"))
      (node (ref "J16") (pin "4") (pinfunction "4_4") (pintype "passive"))
      (node (ref "R4") (pin "P$2") (pinfunction "P$2_P$2") (pintype "bidirectional"))
    )
    (net (code "232") (name "SDO3") (class "Default")
      (node (ref "IC2") (pin "6") (pinfunction "A4_6") (pintype "bidirectional"))
      (node (ref "J4") (pin "6") (pinfunction "6_6") (pintype "passive"))
    )
    (net (code "233") (name "SDOT") (class "Default")
      (node (ref "IC2") (pin "11") (pinfunction "B4_11") (pintype "bidirectional"))
      (node (ref "R4") (pin "P$1") (pinfunction "P$1_P$1") (pintype "bidirectional"))
    )
    (net (code "234") (name "SYSREF1") (class "Default")
      (node (ref "IC1") (pin "M1") (pinfunction "SYSREF+_M1") (pintype "bidirectional"))
      (node (ref "J7") (pin "4") (pinfunction "4_4") (pintype "passive"))
    )
    (net (code "235") (name "SYSREF2") (class "Default")
      (node (ref "IC1") (pin "N1") (pinfunction "SYSREF-_N1") (pintype "bidirectional"))
      (node (ref "J7") (pin "5") (pinfunction "5_5") (pintype "passive"))
    )
    (net (code "236") (name "T2") (class "Default")
      (node (ref "J13") (pin "7") (pinfunction "7_7") (pintype "passive"))
      (node (ref "R47") (pin "P$1") (pinfunction "P$1_P$1") (pintype "bidirectional"))
      (node (ref "X13") (pin "14") (pinfunction "S_14") (pintype "passive"))
    )
    (net (code "237") (name "T4_CLKOUT1N") (class "Default")
      (node (ref "T4_CLKOUT-") (pin "1") (pinfunction "1_1") (pintype "passive"))
      (node (ref "X15") (pin "5") (pinfunction "S_5") (pintype "passive"))
    )
    (net (code "238") (name "TDIODE1") (class "Default")
      (node (ref "IC1") (pin "M2") (pinfunction "TDIODE+_M2") (pintype "bidirectional"))
      (node (ref "J7") (pin "7") (pinfunction "7_7") (pintype "passive"))
    )
    (net (code "239") (name "TDIODE2") (class "Default")
      (node (ref "IC1") (pin "N2") (pinfunction "TDIODE-_N2") (pintype "bidirectional"))
      (node (ref "J7") (pin "8") (pinfunction "8_8") (pintype "passive"))
    )
    (net (code "240") (name "TMSTP1") (class "Default")
      (node (ref "IC1") (pin "D1") (pinfunction "TMSTP+_D1") (pintype "bidirectional"))
      (node (ref "J7") (pin "1") (pinfunction "1_1") (pintype "passive"))
    )
    (net (code "241") (name "TMSTP2") (class "Default")
      (node (ref "IC1") (pin "E1") (pinfunction "TMSTP-_E1") (pintype "bidirectional"))
      (node (ref "J7") (pin "2") (pinfunction "2_2") (pintype "passive"))
    )
    (net (code "242") (name "V11_IN") (class "Default")
      (node (ref "C35") (pin "1") (pinfunction "IN_1") (pintype "bidirectional"))
      (node (ref "C36") (pin "2") (pinfunction "2_2") (pintype "passive"))
      (node (ref "C37") (pin "2") (pinfunction "2_2") (pintype "passive"))
      (node (ref "C45") (pin "1") (pinfunction "IN_1") (pintype "bidirectional"))
      (node (ref "C46") (pin "2") (pinfunction "2_2") (pintype "passive"))
      (node (ref "C47") (pin "2") (pinfunction "2_2") (pintype "passive"))
      (node (ref "J5") (pin "3") (pinfunction "3_3") (pintype "passive"))
      (node (ref "J5") (pin "5") (pinfunction "5_5") (pintype "passive"))
    )
    (net (code "243") (name "V19_IN") (class "Default")
      (node (ref "C15") (pin "1") (pinfunction "IN_1") (pintype "bidirectional"))
      (node (ref "C16") (pin "2") (pinfunction "2_2") (pintype "passive"))
      (node (ref "C17") (pin "2") (pinfunction "2_2") (pintype "passive"))
      (node (ref "C25") (pin "1") (pinfunction "IN_1") (pintype "bidirectional"))
      (node (ref "C26") (pin "2") (pinfunction "2_2") (pintype "passive"))
      (node (ref "C27") (pin "2") (pinfunction "2_2") (pintype "passive"))
      (node (ref "J5") (pin "7") (pinfunction "7_7") (pintype "passive"))
    )
    (net (code "244") (name "VA11") (class "Default")
      (node (ref "C21") (pin "2") (pinfunction "2_2") (pintype "passive"))
      (node (ref "C22") (pin "2") (pinfunction "2_2") (pintype "passive"))
      (node (ref "C23") (pin "2") (pinfunction "2_2") (pintype "passive"))
      (node (ref "C32") (pin "2") (pinfunction "2_2") (pintype "passive"))
      (node (ref "C33") (pin "2") (pinfunction "2_2") (pintype "passive"))
      (node (ref "C35") (pin "3") (pinfunction "OUT_3") (pintype "bidirectional"))
      (node (ref "C38") (pin "2") (pinfunction "2_2") (pintype "passive"))
      (node (ref "C39") (pin "2") (pinfunction "2_2") (pintype "passive"))
      (node (ref "IC1") (pin "E4") (pinfunction "VA11_1_E4") (pintype "bidirectional"))
      (node (ref "IC1") (pin "E5") (pinfunction "VA11_2_E5") (pintype "bidirectional"))
      (node (ref "IC1") (pin "E6") (pinfunction "VA11_3_E6") (pintype "bidirectional"))
      (node (ref "IC1") (pin "F3") (pinfunction "VA11_4_F3") (pintype "bidirectional"))
      (node (ref "IC1") (pin "F4") (pinfunction "VA11_5_F4") (pintype "bidirectional"))
      (node (ref "IC1") (pin "F5") (pinfunction "VA11_6_F5") (pintype "bidirectional"))
      (node (ref "IC1") (pin "F6") (pinfunction "VA11_7_F6") (pintype "bidirectional"))
      (node (ref "IC1") (pin "L3") (pinfunction "VA11_8_L3") (pintype "bidirectional"))
      (node (ref "IC1") (pin "L4") (pinfunction "VA11_9_L4") (pintype "bidirectional"))
      (node (ref "IC1") (pin "L5") (pinfunction "VA11_10_L5") (pintype "bidirectional"))
      (node (ref "IC1") (pin "L6") (pinfunction "VA11_11_L6") (pintype "bidirectional"))
      (node (ref "IC1") (pin "M4") (pinfunction "VA11_12_M4") (pintype "bidirectional"))
      (node (ref "IC1") (pin "M5") (pinfunction "VA11_13_M5") (pintype "bidirectional"))
      (node (ref "IC1") (pin "M6") (pinfunction "VA11_14_M6") (pintype "bidirectional"))
      (node (ref "J3") (pin "1") (pinfunction "1_1") (pintype "passive"))
      (node (ref "J3") (pin "2") (pinfunction "2_2") (pintype "passive"))
      (node (ref "J3") (pin "3") (pinfunction "3_3") (pintype "passive"))
      (node (ref "J3") (pin "4") (pinfunction "4_4") (pintype "passive"))
    )
    (net (code "245") (name "VA19") (class "Default")
      (node (ref "C13") (pin "2") (pinfunction "2_2") (pintype "passive"))
      (node (ref "C14") (pin "2") (pinfunction "2_2") (pintype "passive"))
      (node (ref "C20") (pin "2") (pinfunction "2_2") (pintype "passive"))
      (node (ref "C25") (pin "3") (pinfunction "OUT_3") (pintype "bidirectional"))
      (node (ref "C28") (pin "2") (pinfunction "2_2") (pintype "passive"))
      (node (ref "C29") (pin "2") (pinfunction "2_2") (pintype "passive"))
      (node (ref "IC1") (pin "G3") (pinfunction "VA19_1_G3") (pintype "bidirectional"))
      (node (ref "IC1") (pin "G4") (pinfunction "VA19_2_G4") (pintype "bidirectional"))
      (node (ref "IC1") (pin "G5") (pinfunction "VA19_3_G5") (pintype "bidirectional"))
      (node (ref "IC1") (pin "G6") (pinfunction "VA19_4_G6") (pintype "bidirectional"))
      (node (ref "IC1") (pin "H3") (pinfunction "VA19_5_H3") (pintype "bidirectional"))
      (node (ref "IC1") (pin "H4") (pinfunction "VA19_6_H4") (pintype "bidirectional"))
      (node (ref "IC1") (pin "H5") (pinfunction "VA19_7_H5") (pintype "bidirectional"))
      (node (ref "IC1") (pin "H6") (pinfunction "VA19_8_H6") (pintype "bidirectional"))
      (node (ref "IC1") (pin "J3") (pinfunction "VA19_9_J3") (pintype "bidirectional"))
      (node (ref "IC1") (pin "J4") (pinfunction "VA19_10_J4") (pintype "bidirectional"))
      (node (ref "IC1") (pin "J5") (pinfunction "VA19_11_J5") (pintype "bidirectional"))
      (node (ref "IC1") (pin "J6") (pinfunction "VA19_12_J6") (pintype "bidirectional"))
      (node (ref "IC1") (pin "K3") (pinfunction "VA19_13_K3") (pintype "bidirectional"))
      (node (ref "IC1") (pin "K4") (pinfunction "VA19_14_K4") (pintype "bidirectional"))
      (node (ref "IC1") (pin "K5") (pinfunction "VA19_15_K5") (pintype "bidirectional"))
      (node (ref "IC1") (pin "K6") (pinfunction "VA19_16_K6") (pintype "bidirectional"))
      (node (ref "J1") (pin "5") (pinfunction "5_5") (pintype "passive"))
      (node (ref "J1") (pin "6") (pinfunction "6_6") (pintype "passive"))
      (node (ref "J1") (pin "7") (pinfunction "7_7") (pintype "passive"))
      (node (ref "J1") (pin "8") (pinfunction "8_8") (pintype "passive"))
      (node (ref "J12") (pin "4") (pinfunction "4_4") (pintype "passive"))
      (node (ref "R42") (pin "P$1") (pinfunction "P$1_P$1") (pintype "bidirectional"))
    )
    (net (code "246") (name "VD11") (class "Default")
      (node (ref "C24") (pin "2") (pinfunction "2_2") (pintype "passive"))
      (node (ref "C30") (pin "2") (pinfunction "2_2") (pintype "passive"))
      (node (ref "C31") (pin "2") (pinfunction "2_2") (pintype "passive"))
      (node (ref "C45") (pin "3") (pinfunction "OUT_3") (pintype "bidirectional"))
      (node (ref "C48") (pin "2") (pinfunction "2_2") (pintype "passive"))
      (node (ref "C49") (pin "2") (pinfunction "2_2") (pintype "passive"))
      (node (ref "IC1") (pin "E8") (pinfunction "VD11_1_E8") (pintype "bidirectional"))
      (node (ref "IC1") (pin "F8") (pinfunction "VD11_2_F8") (pintype "bidirectional"))
      (node (ref "IC1") (pin "G8") (pinfunction "VD11_3_G8") (pintype "bidirectional"))
      (node (ref "IC1") (pin "K8") (pinfunction "VD11_4_K8") (pintype "bidirectional"))
      (node (ref "IC1") (pin "L8") (pinfunction "VD11_5_L8") (pintype "bidirectional"))
      (node (ref "IC1") (pin "M8") (pinfunction "VD11_6_M8") (pintype "bidirectional"))
      (node (ref "J3") (pin "5") (pinfunction "5_5") (pintype "passive"))
      (node (ref "J3") (pin "6") (pinfunction "6_6") (pintype "passive"))
      (node (ref "J3") (pin "7") (pinfunction "7_7") (pintype "passive"))
      (node (ref "J3") (pin "8") (pinfunction "8_8") (pintype "passive"))
    )
    (net (code "247") (name "VDDD33") (class "Default")
      (node (ref "C3") (pin "2") (pinfunction "2_2") (pintype "passive"))
      (node (ref "IC2") (pin "1") (pinfunction "DIR1_1") (pintype "bidirectional"))
      (node (ref "IC2") (pin "16") (pinfunction "VCCA_16") (pintype "bidirectional"))
      (node (ref "IC2") (pin "2") (pinfunction "DIR2_2") (pintype "bidirectional"))
      (node (ref "IC2") (pin "7") (pinfunction "DIR3_7") (pintype "bidirectional"))
      (node (ref "J12") (pin "2") (pinfunction "2_2") (pintype "passive"))
      (node (ref "J2") (pin "3") (pinfunction "3_3") (pintype "passive"))
      (node (ref "J2") (pin "4") (pinfunction "4_4") (pintype "passive"))
      (node (ref "J4") (pin "1") (pinfunction "1_1") (pintype "passive"))
      (node (ref "J4") (pin "7") (pinfunction "7_7") (pintype "passive"))
      (node (ref "R44") (pin "P$1") (pinfunction "P$1_P$1") (pintype "bidirectional"))
    )
    (net (code "248") (name "VDDL19") (class "Default")
      (node (ref "C15") (pin "3") (pinfunction "OUT_3") (pintype "bidirectional"))
      (node (ref "C18") (pin "2") (pinfunction "2_2") (pintype "passive"))
      (node (ref "C19") (pin "2") (pinfunction "2_2") (pintype "passive"))
      (node (ref "C4") (pin "2") (pinfunction "2_2") (pintype "passive"))
      (node (ref "IC2") (pin "15") (pinfunction "VCCB_15") (pintype "bidirectional"))
      (node (ref "J12") (pin "3") (pinfunction "3_3") (pintype "passive"))
      (node (ref "J2") (pin "1") (pinfunction "1_1") (pintype "passive"))
      (node (ref "J2") (pin "2") (pinfunction "2_2") (pintype "passive"))
      (node (ref "R43") (pin "P$1") (pinfunction "P$1_P$1") (pintype "bidirectional"))
      (node (ref "R5") (pin "P$1") (pinfunction "P$1_P$1") (pintype "bidirectional"))
    )
    (net (code "249") (name "VLVDS") (class "Default")
      (node (ref "C10") (pin "2") (pinfunction "2_2") (pintype "passive"))
      (node (ref "C11") (pin "2") (pinfunction "2_2") (pintype "passive"))
      (node (ref "C12") (pin "2") (pinfunction "2_2") (pintype "passive"))
      (node (ref "C5") (pin "3") (pinfunction "OUT_3") (pintype "bidirectional"))
      (node (ref "C8") (pin "2") (pinfunction "2_2") (pintype "passive"))
      (node (ref "C9") (pin "2") (pinfunction "2_2") (pintype "passive"))
      (node (ref "IC1") (pin "G11") (pinfunction "VLVDS_1_G11") (pintype "bidirectional"))
      (node (ref "IC1") (pin "G12") (pinfunction "VLVDS_2_G12") (pintype "bidirectional"))
      (node (ref "IC1") (pin "H11") (pinfunction "VLVDS_3_H11") (pintype "bidirectional"))
      (node (ref "IC1") (pin "H12") (pinfunction "VLVDS_4_H12") (pintype "bidirectional"))
      (node (ref "IC1") (pin "H13") (pinfunction "VLVDS_5_H13") (pintype "bidirectional"))
      (node (ref "IC1") (pin "J11") (pinfunction "VLVDS_6_J11") (pintype "bidirectional"))
      (node (ref "IC1") (pin "J12") (pinfunction "VLVDS_7_J12") (pintype "bidirectional"))
      (node (ref "IC1") (pin "J13") (pinfunction "VLVDS_8_J13") (pintype "bidirectional"))
      (node (ref "IC1") (pin "K11") (pinfunction "VLVDS_9_K11") (pintype "bidirectional"))
      (node (ref "IC1") (pin "K12") (pinfunction "VLVDS_10_K12") (pintype "bidirectional"))
      (node (ref "J1") (pin "1") (pinfunction "1_1") (pintype "passive"))
      (node (ref "J1") (pin "2") (pinfunction "2_2") (pintype "passive"))
      (node (ref "J1") (pin "3") (pinfunction "3_3") (pintype "passive"))
      (node (ref "J1") (pin "4") (pinfunction "4_4") (pintype "passive"))
    )
    (net (code "250") (name "VLVDS_IN") (class "Default")
      (node (ref "C5") (pin "1") (pinfunction "IN_1") (pintype "bidirectional"))
      (node (ref "C6") (pin "2") (pinfunction "2_2") (pintype "passive"))
      (node (ref "C7") (pin "2") (pinfunction "2_2") (pintype "passive"))
      (node (ref "J5") (pin "2") (pinfunction "2_2") (pintype "passive"))
    )
    (net (code "251") (name "unconnected-(X14T-S-Pad27)") (class "Default")
      (node (ref "X14") (pin "27") (pinfunction "S_27") (pintype "passive"))
    )
    (net (code "252") (name "unconnected-(X14U-S-Pad28)") (class "Default")
      (node (ref "X14") (pin "28") (pinfunction "S_28") (pintype "passive"))
    )
    (net (code "253") (name "unconnected-(X17T-S-Pad27)") (class "Default")
      (node (ref "X17") (pin "27") (pinfunction "S_27") (pintype "passive"))
    )
    (net (code "254") (name "unconnected-(X17U-S-Pad28)") (class "Default")
      (node (ref "X17") (pin "28") (pinfunction "S_28") (pintype "passive"))
    )
  )
)
